# 20160428.net
KiCad netlist of a schematic drawn in Altium Designer
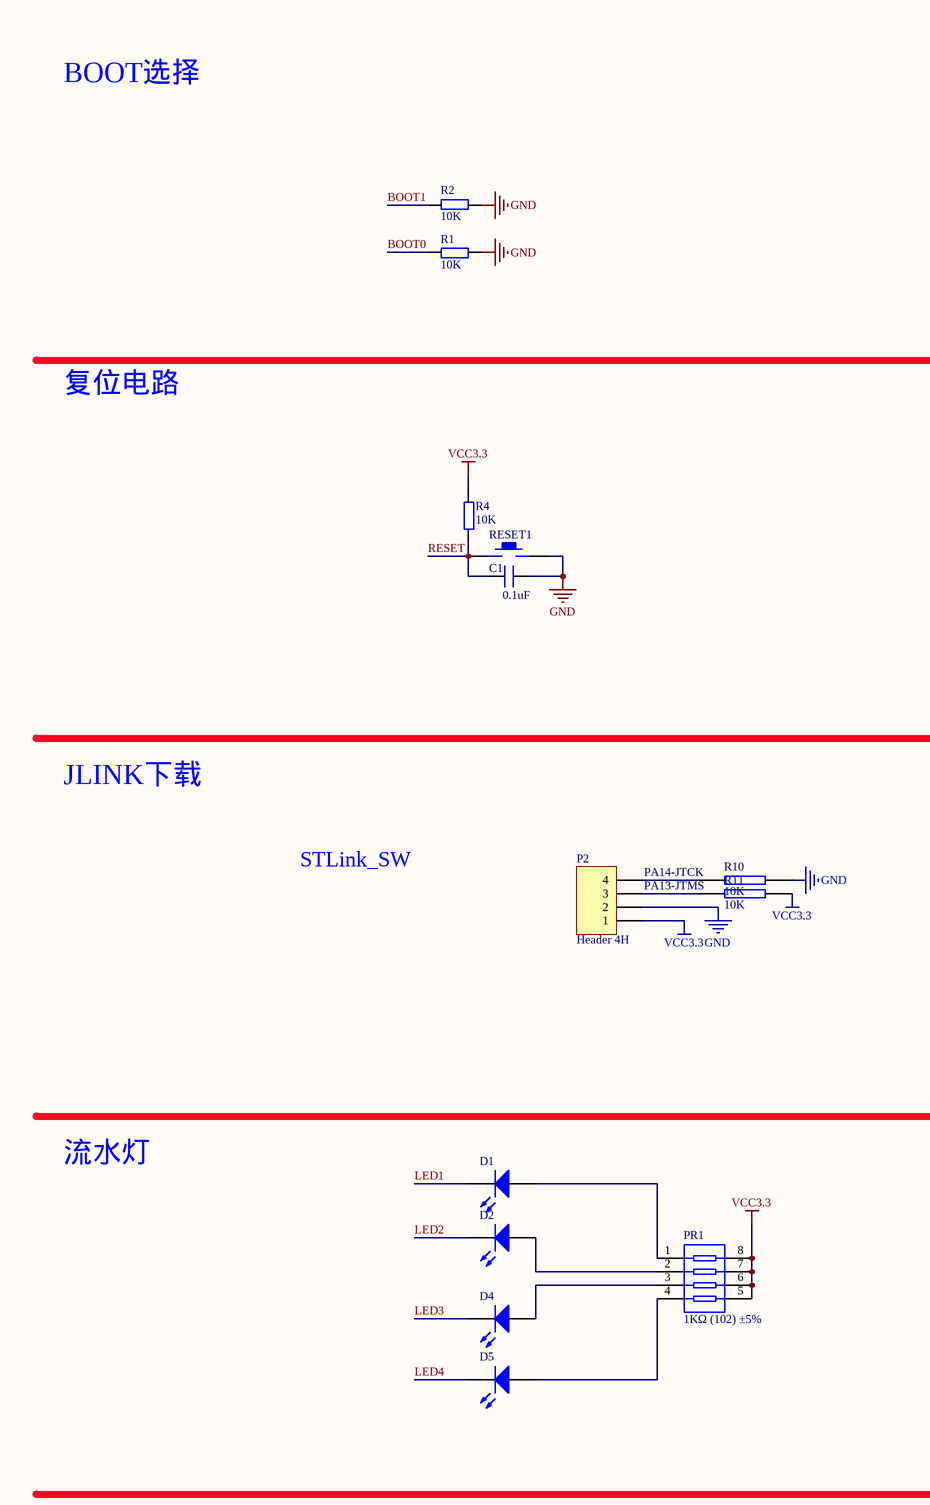
[diagram p0: 主控板20160428.SchDoc, top left]
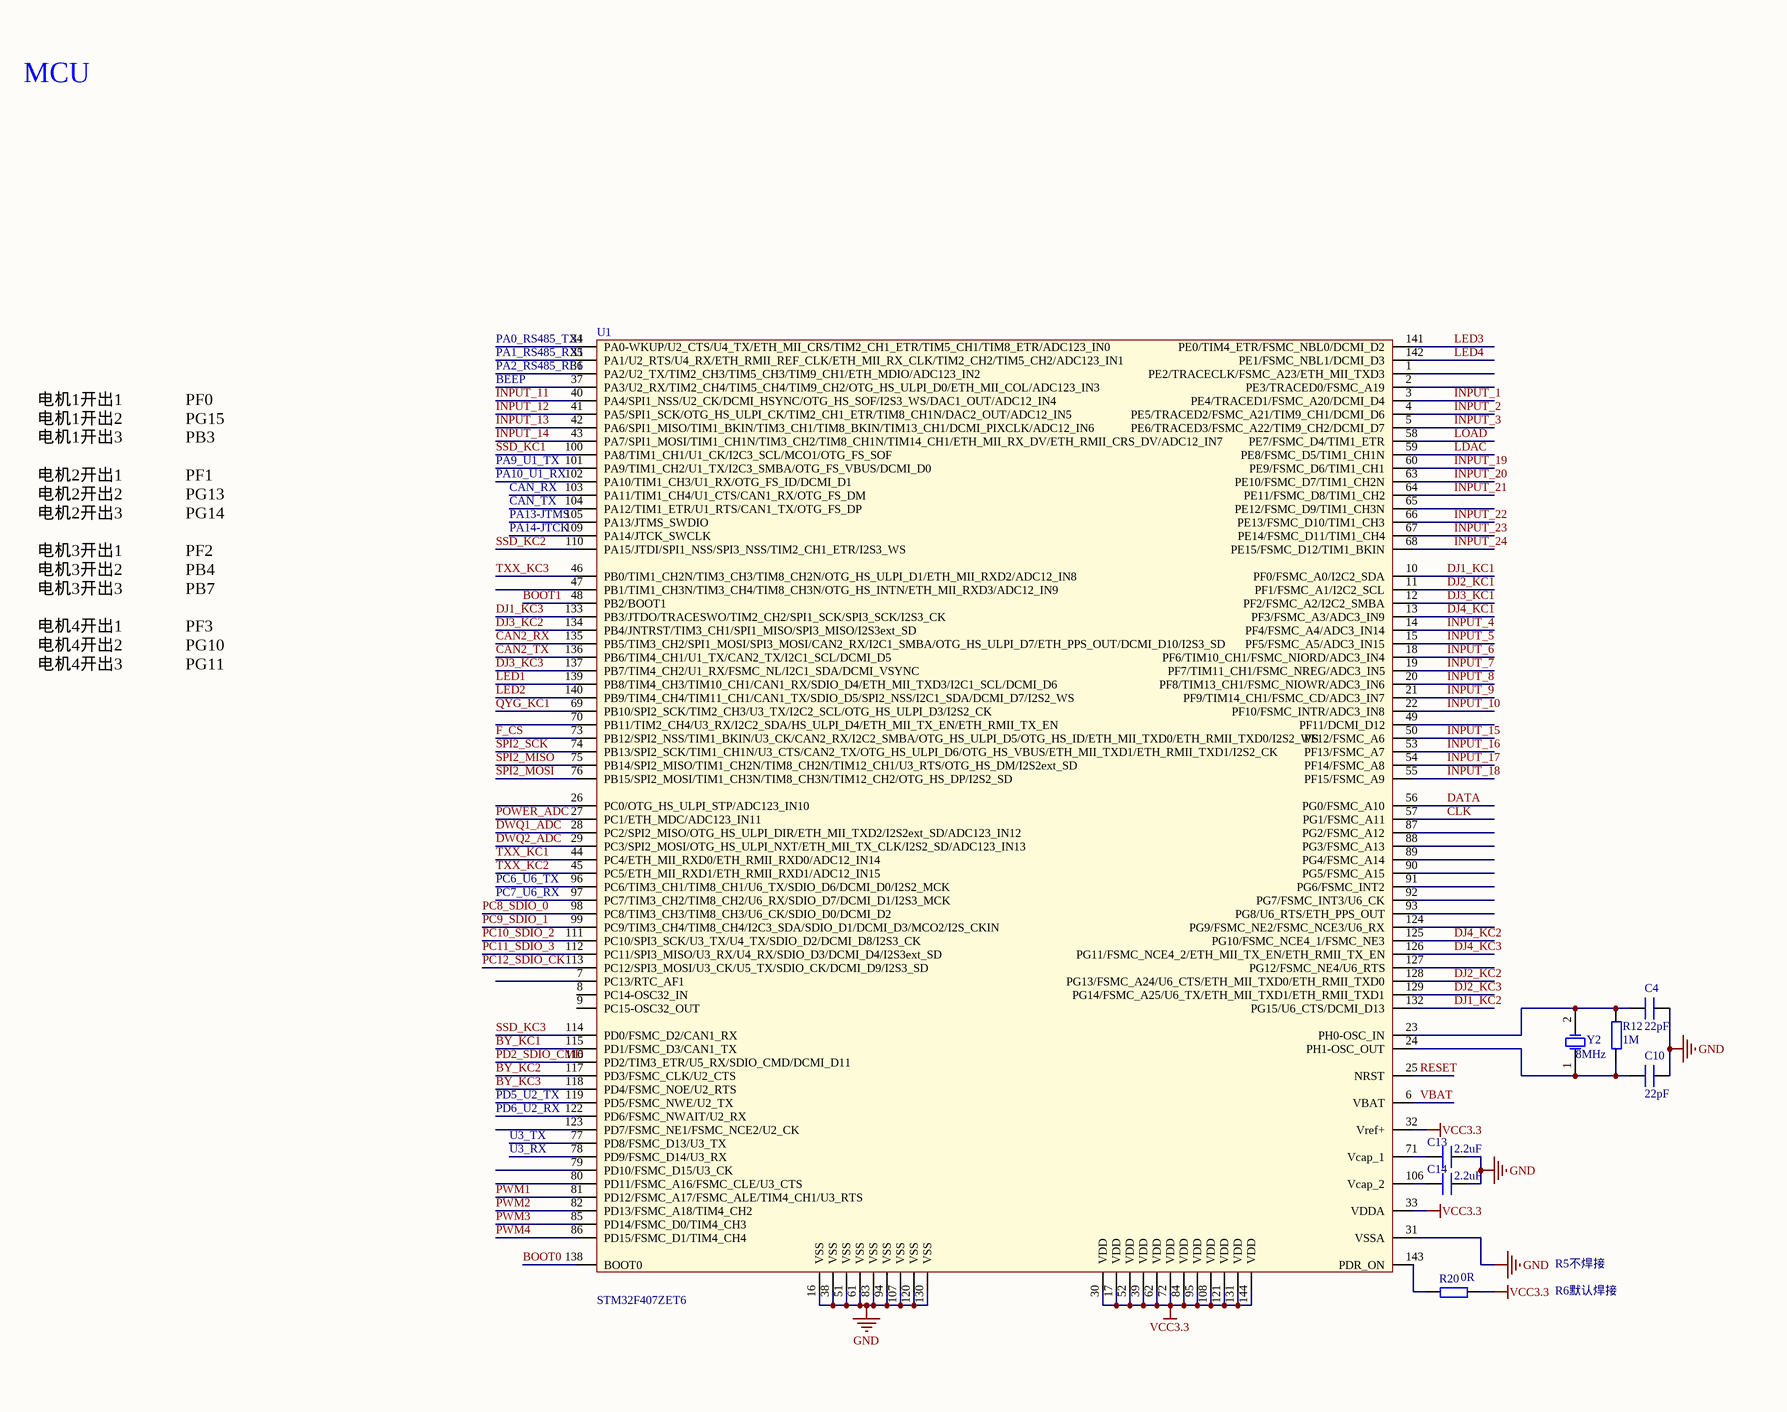
[diagram p1: 主控板20160428.SchDoc, top middle]
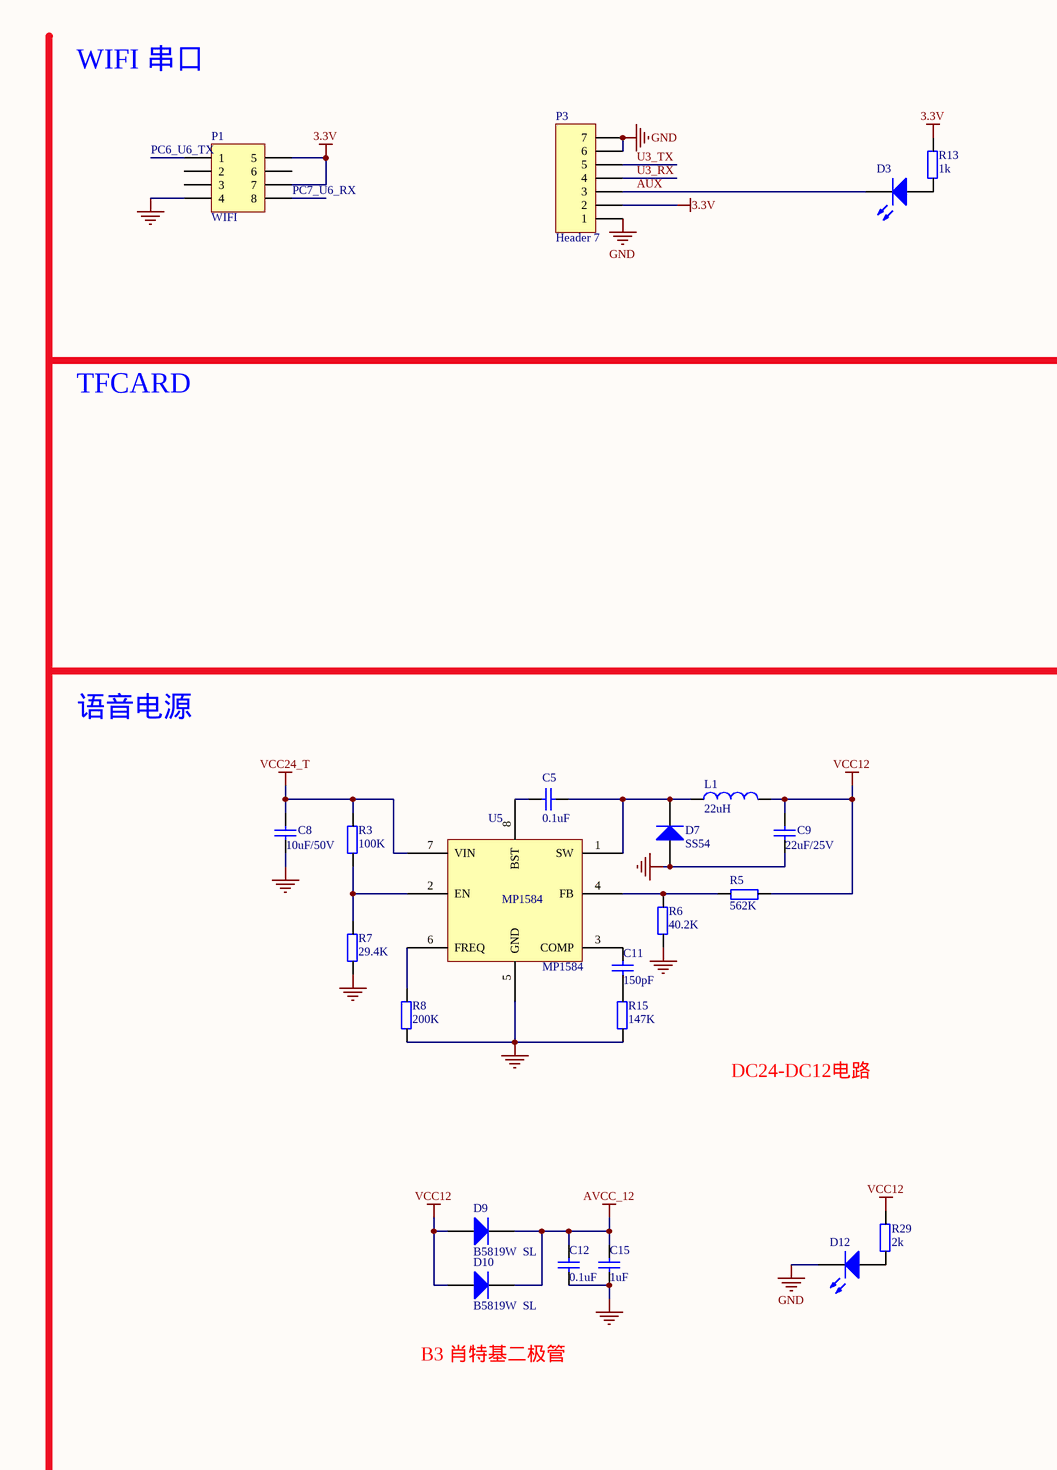
[diagram p2: 主控板20160428.SchDoc, top right]
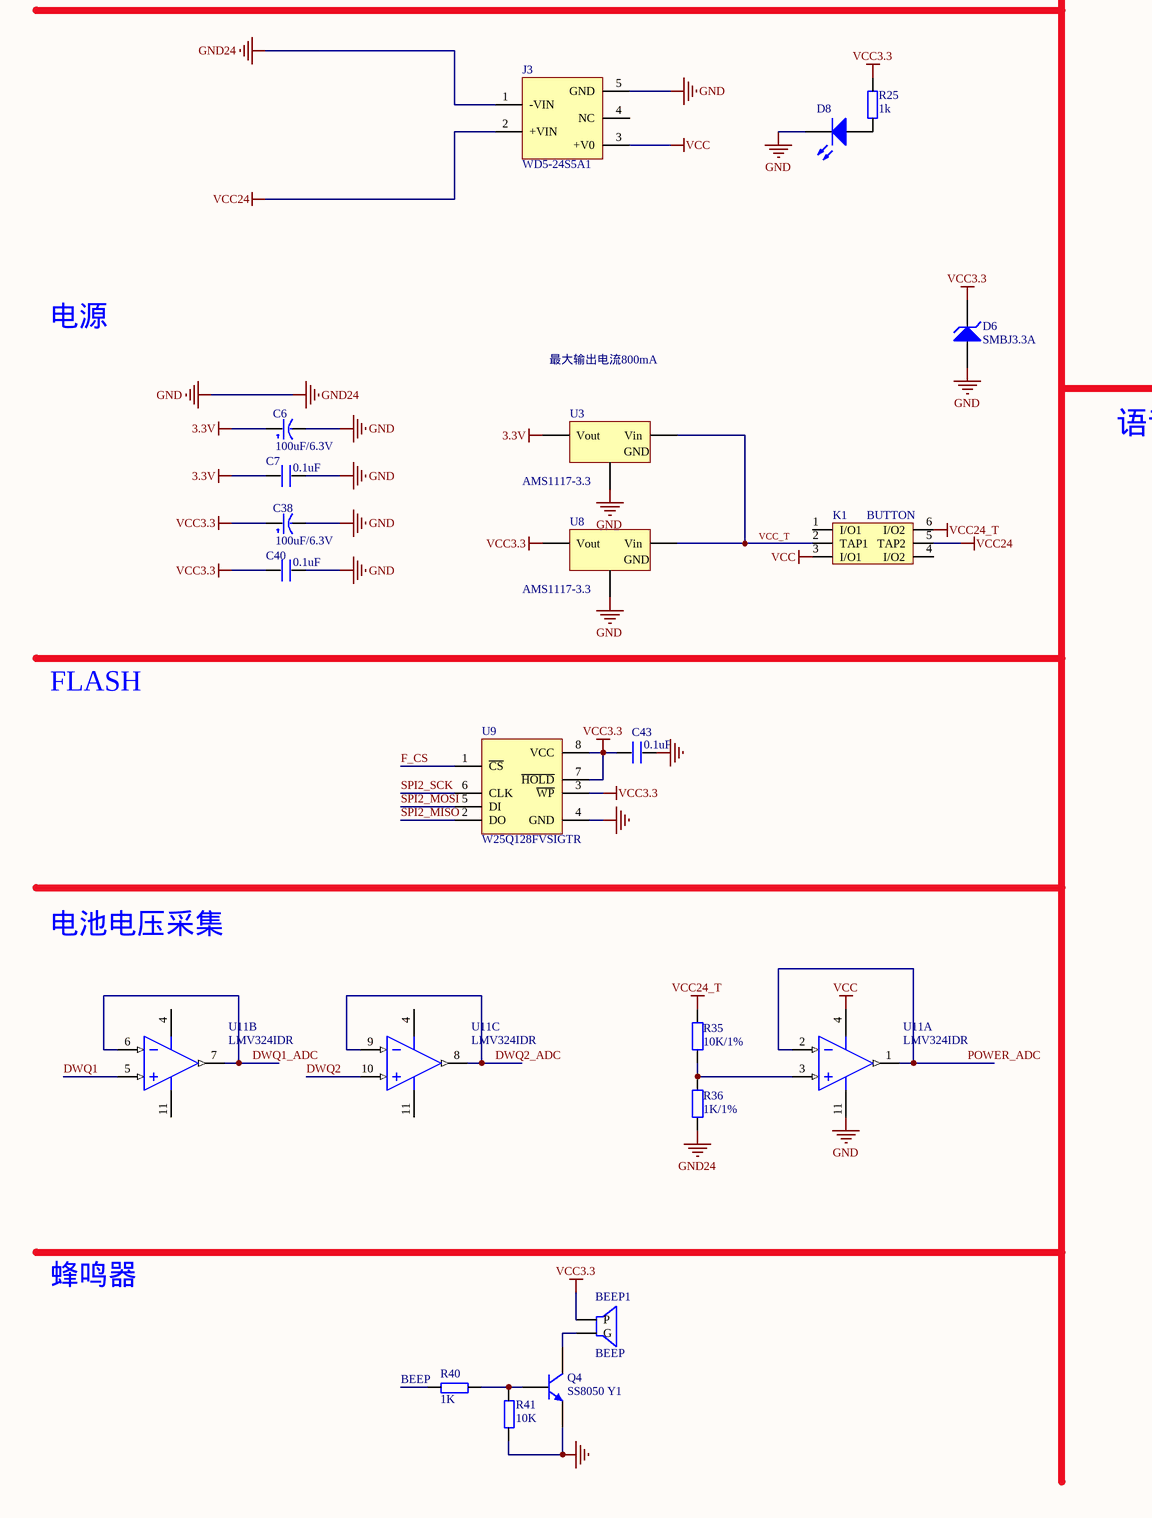
[diagram p3: 主控板20160428.SchDoc, bottom left]
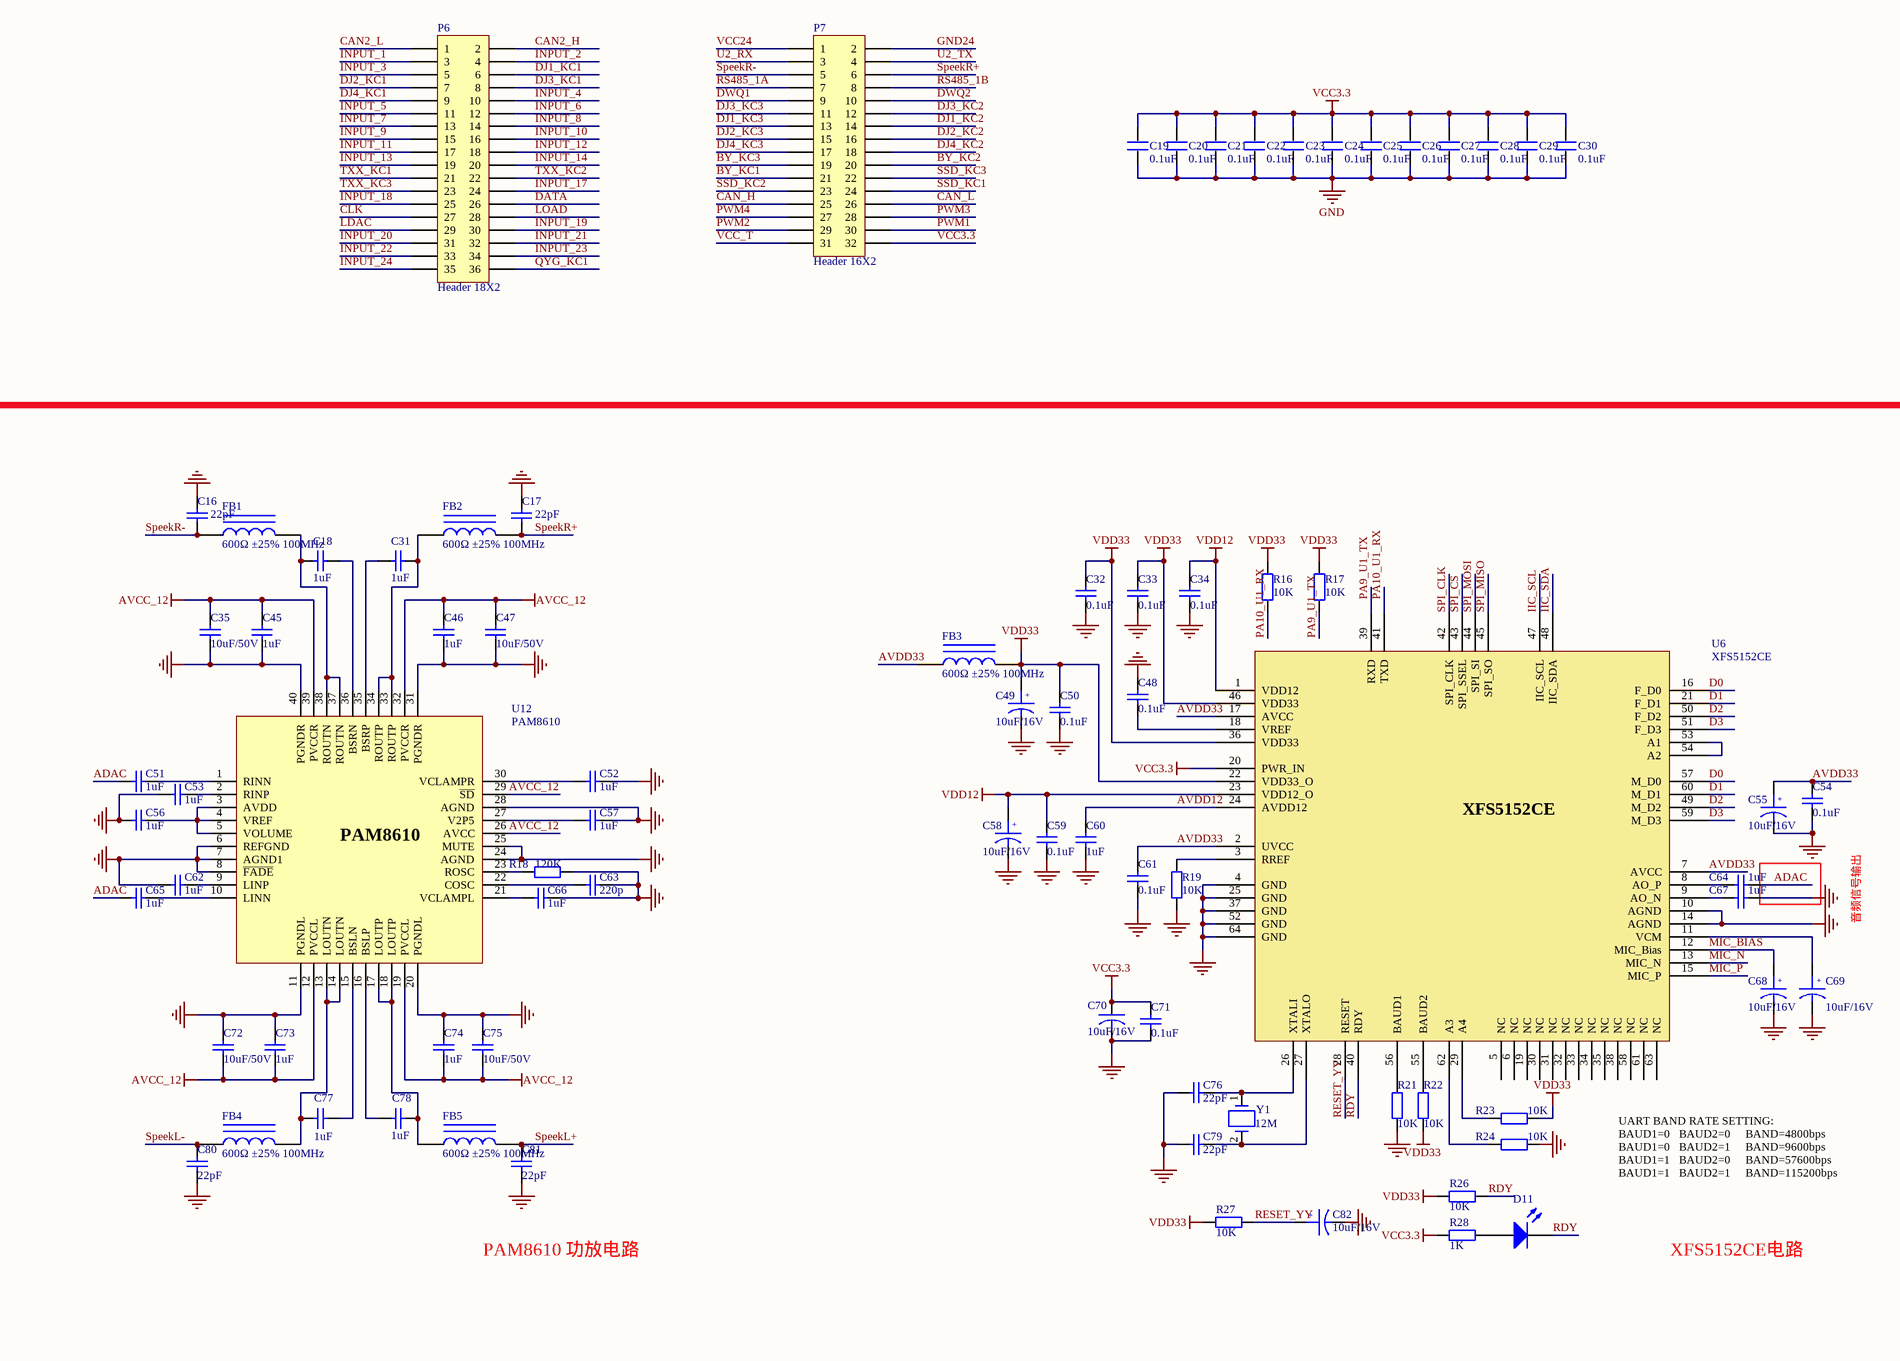
[diagram p4: 主控板20160428.SchDoc, bottom middle]
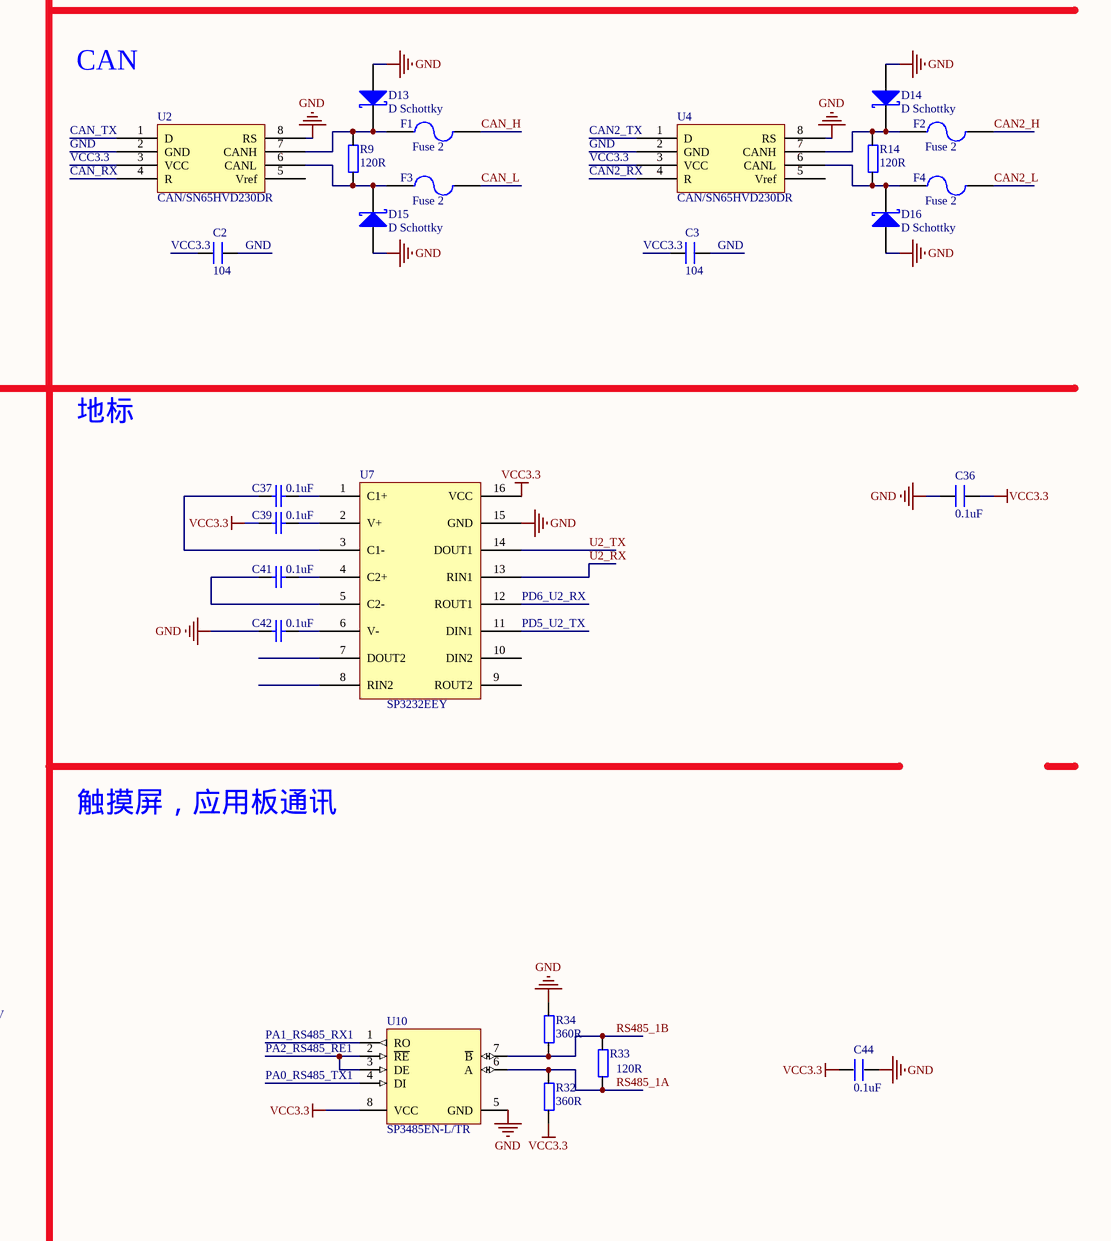
[diagram p5: 主控板20160428.SchDoc, bottom right]

(export (version "E")
  (design (tool "Eeschema 10.0.6"))
  (components
    (comp (ref "BEEP1") (value "BEEP") (footprint "BELL-5") (libsource (lib "WarShip V3_SCH") (part "BEEP")))
    (comp (ref "C1") (value "0.1uF") (footprint "C0805") (libsource (lib "Explorer STM32F407封装库") (part "C")))
    (comp (ref "C2") (value "104") (footprint "C0805") (libsource (lib "Explorer STM32F407封装库") (part "C_3")))
    (comp (ref "C3") (value "104") (footprint "C0805") (libsource (lib "Explorer STM32F407封装库") (part "C_3")))
    (comp (ref "C4")
      (value "22pF")
      (footprint "C0805")
      (libsource (lib "Explorer STM32F407封装库") (part "C_3"))
    )
    (comp (ref "C5")
      (value "0.1uF")
      (footprint "0603_C")
      (description "Capacitor (Semiconductor SIM Model)")
      (fields (field (name "PUBLISHER") "Altium Limited"))
      (libsource (lib "Miscellaneous Devices") (part "Cap Semi"))
    )
    (comp (ref "C6")
      (value "100uF/6.3V")
      (footprint "CASE-B_3528")
      (libsource (lib "WarShip V3_SCH") (part "CAP"))
    )
    (comp (ref "C7") (value "0.1uF") (footprint "C0805") (libsource (lib "WarShip V3_SCH") (part "C")))
    (comp (ref "C8")
      (value "10uF/50V")
      (footprint "1206_C")
      (description "Capacitor (Semiconductor SIM Model)")
      (fields (field (name "PUBLISHER") "Altium Limited"))
      (libsource (lib "Miscellaneous Devices") (part "Cap Semi"))
    )
    (comp (ref "C9")
      (value "22uF/25V")
      (footprint "0805_C")
      (description "Capacitor (Semiconductor SIM Model)")
      (fields (field (name "PUBLISHER") "Altium Limited"))
      (libsource (lib "Miscellaneous Devices") (part "Cap Semi"))
    )
    (comp (ref "C10")
      (value "22pF")
      (footprint "C0805")
      (libsource (lib "Explorer STM32F407封装库") (part "C_3"))
    )
    (comp (ref "C11")
      (value "150pF")
      (footprint "0603_C")
      (description "Capacitor (Semiconductor SIM Model)")
      (fields (field (name "PUBLISHER") "Altium Limited"))
      (libsource (lib "Miscellaneous Devices") (part "Cap Semi"))
    )
    (comp (ref "C12")
      (value "0.1uF")
      (footprint "0603_C")
      (description "Capacitor (Semiconductor SIM Model)")
      (fields (field (name "PUBLISHER") "Altium Limited"))
      (libsource (lib "Miscellaneous Devices") (part "Cap Semi"))
    )
    (comp (ref "C13")
      (value "2.2uF")
      (footprint "C0805")
      (libsource (lib "Explorer STM32F407封装库") (part "C"))
    )
    (comp (ref "C14")
      (value "2.2uF")
      (footprint "C0805")
      (libsource (lib "Explorer STM32F407封装库") (part "C"))
    )
    (comp (ref "C15")
      (value "1uF")
      (footprint "0603_C")
      (description "Capacitor (Semiconductor SIM Model)")
      (fields (field (name "PUBLISHER") "Altium Limited"))
      (libsource (lib "Miscellaneous Devices") (part "Cap Semi"))
    )
    (comp (ref "C16")
      (value "22pF")
      (footprint "0603_C")
      (description "Capacitor (Semiconductor SIM Model)")
      (fields (field (name "PUBLISHER") "Altium Limited"))
      (libsource (lib "Miscellaneous Devices") (part "Cap Semi"))
    )
    (comp (ref "C17")
      (value "22pF")
      (footprint "0603_C")
      (description "Capacitor (Semiconductor SIM Model)")
      (fields (field (name "PUBLISHER") "Altium Limited"))
      (libsource (lib "Miscellaneous Devices") (part "Cap Semi"))
    )
    (comp (ref "C18")
      (value "1uF")
      (footprint "0603_C")
      (description "Capacitor (Semiconductor SIM Model)")
      (fields (field (name "PUBLISHER") "Altium Limited"))
      (libsource (lib "Miscellaneous Devices") (part "Cap Semi"))
    )
    (comp (ref "C19") (value "0.1uF") (footprint "C0805") (libsource (lib "WarShip V3_SCH") (part "C")))
    (comp (ref "C20") (value "0.1uF") (footprint "C0805") (libsource (lib "WarShip V3_SCH") (part "C")))
    (comp (ref "C21") (value "0.1uF") (footprint "C0805") (libsource (lib "WarShip V3_SCH") (part "C")))
    (comp (ref "C22") (value "0.1uF") (footprint "C0805") (libsource (lib "WarShip V3_SCH") (part "C")))
    (comp (ref "C23") (value "0.1uF") (footprint "C0805") (libsource (lib "WarShip V3_SCH") (part "C")))
    (comp (ref "C24") (value "0.1uF") (footprint "C0805") (libsource (lib "WarShip V3_SCH") (part "C")))
    (comp (ref "C25") (value "0.1uF") (footprint "C0805") (libsource (lib "WarShip V3_SCH") (part "C")))
    (comp (ref "C26") (value "0.1uF") (footprint "C0805") (libsource (lib "WarShip V3_SCH") (part "C")))
    (comp (ref "C27") (value "0.1uF") (footprint "C0805") (libsource (lib "WarShip V3_SCH") (part "C")))
    (comp (ref "C28") (value "0.1uF") (footprint "C0805") (libsource (lib "WarShip V3_SCH") (part "C")))
    (comp (ref "C29") (value "0.1uF") (footprint "C0805") (libsource (lib "WarShip V3_SCH") (part "C")))
    (comp (ref "C30") (value "0.1uF") (footprint "C0805") (libsource (lib "WarShip V3_SCH") (part "C")))
    (comp (ref "C31")
      (value "1uF")
      (footprint "0603_C")
      (description "Capacitor (Semiconductor SIM Model)")
      (fields (field (name "PUBLISHER") "Altium Limited"))
      (libsource (lib "Miscellaneous Devices") (part "Cap Semi"))
    )
    (comp (ref "C32")
      (value "0.1uF")
      (footprint "0603_C")
      (description "Capacitor (Semiconductor SIM Model)")
      (fields (field (name "PUBLISHER") "Altium Limited"))
      (libsource (lib "Miscellaneous Devices") (part "Cap Semi"))
    )
    (comp (ref "C33")
      (value "0.1uF")
      (footprint "0603_C")
      (description "Capacitor (Semiconductor SIM Model)")
      (fields (field (name "PUBLISHER") "Altium Limited"))
      (libsource (lib "Miscellaneous Devices") (part "Cap Semi"))
    )
    (comp (ref "C34")
      (value "0.1uF")
      (footprint "0603_C")
      (description "Capacitor (Semiconductor SIM Model)")
      (fields (field (name "PUBLISHER") "Altium Limited"))
      (libsource (lib "Miscellaneous Devices") (part "Cap Semi"))
    )
    (comp (ref "C35")
      (value "10uF/50V")
      (footprint "1206_C")
      (description "电容")
      (fields (field (name "PUBLISHER") "Altium Limited"))
      (libsource (lib "*") (part "Cap NP"))
    )
    (comp (ref "C36")
      (value "0.1uF")
      (footprint "C0805")
      (libsource (lib "Explorer STM32F407封装库") (part "C_2"))
    )
    (comp (ref "C37")
      (value "0.1uF")
      (footprint "C0805")
      (description "Capacitor")
      (fields (field (name "PUBLISHER") "Altium Limited"))
      (libsource (lib "Miscellaneous Devices") (part "Cap"))
    )
    (comp (ref "C38")
      (value "100uF/6.3V")
      (footprint "CASE-B_3528")
      (libsource (lib "WarShip V3_SCH") (part "CAP"))
    )
    (comp (ref "C39")
      (value "0.1uF")
      (footprint "C0805")
      (description "Capacitor")
      (fields (field (name "PUBLISHER") "Altium Limited"))
      (libsource (lib "Miscellaneous Devices") (part "Cap"))
    )
    (comp (ref "C40") (value "0.1uF") (footprint "C0805") (libsource (lib "WarShip V3_SCH") (part "C")))
    (comp (ref "C41")
      (value "0.1uF")
      (footprint "C0805")
      (description "Capacitor")
      (fields (field (name "PUBLISHER") "Altium Limited"))
      (libsource (lib "Miscellaneous Devices") (part "Cap"))
    )
    (comp (ref "C42")
      (value "0.1uF")
      (footprint "C0805")
      (description "Capacitor")
      (fields (field (name "PUBLISHER") "Altium Limited"))
      (libsource (lib "Miscellaneous Devices") (part "Cap"))
    )
    (comp (ref "C43") (value "0.1uF") (footprint "C0805") (libsource (lib "WarShip V3_SCH") (part "C")))
    (comp (ref "C44")
      (value "0.1uF")
      (footprint "C0805")
      (libsource (lib "Explorer STM32F407封装库") (part "C_3"))
    )
    (comp (ref "C45")
      (value "1uF")
      (footprint "0603_C")
      (description "Capacitor (Semiconductor SIM Model)")
      (fields (field (name "PUBLISHER") "Altium Limited"))
      (libsource (lib "Miscellaneous Devices") (part "Cap Semi"))
    )
    (comp (ref "C46")
      (value "1uF")
      (footprint "0603_C")
      (description "Capacitor (Semiconductor SIM Model)")
      (fields (field (name "PUBLISHER") "Altium Limited"))
      (libsource (lib "Miscellaneous Devices") (part "Cap Semi"))
    )
    (comp (ref "C47")
      (value "10uF/50V")
      (footprint "1206_C")
      (description "电容")
      (fields (field (name "PUBLISHER") "Altium Limited"))
      (libsource (lib "*") (part "Cap NP"))
    )
    (comp (ref "C48")
      (value "0.1uF")
      (footprint "0603_C")
      (description "Capacitor (Semiconductor SIM Model)")
      (fields (field (name "PUBLISHER") "Altium Limited"))
      (libsource (lib "Miscellaneous Devices") (part "Cap Semi"))
    )
    (comp (ref "C49") (value "10uF/16V") (footprint "3216") (libsource (lib "*") (part "CAP POL")))
    (comp (ref "C50")
      (value "0.1uF")
      (footprint "0603_C")
      (description "Capacitor (Semiconductor SIM Model)")
      (fields (field (name "PUBLISHER") "Altium Limited"))
      (libsource (lib "Miscellaneous Devices") (part "Cap Semi"))
    )
    (comp (ref "C51")
      (value "1uF")
      (footprint "0603_C")
      (description "Capacitor (Semiconductor SIM Model)")
      (fields (field (name "PUBLISHER") "Altium Limited"))
      (libsource (lib "Miscellaneous Devices") (part "Cap Semi"))
    )
    (comp (ref "C52")
      (value "1uF")
      (footprint "0603_C")
      (description "Capacitor (Semiconductor SIM Model)")
      (fields (field (name "PUBLISHER") "Altium Limited"))
      (libsource (lib "Miscellaneous Devices") (part "Cap Semi"))
    )
    (comp (ref "C53")
      (value "1uF")
      (footprint "0603_C")
      (description "Capacitor (Semiconductor SIM Model)")
      (fields (field (name "PUBLISHER") "Altium Limited"))
      (libsource (lib "Miscellaneous Devices") (part "Cap Semi"))
    )
    (comp (ref "C54")
      (value "0.1uF")
      (footprint "0603_C")
      (description "Capacitor (Semiconductor SIM Model)")
      (fields (field (name "PUBLISHER") "Altium Limited"))
      (libsource (lib "Miscellaneous Devices") (part "Cap Semi"))
    )
    (comp (ref "C55") (value "10uF/16V") (footprint "3216") (libsource (lib "*") (part "CAP POL")))
    (comp (ref "C56")
      (value "1uF")
      (footprint "0603_C")
      (description "Capacitor (Semiconductor SIM Model)")
      (fields (field (name "PUBLISHER") "Altium Limited"))
      (libsource (lib "Miscellaneous Devices") (part "Cap Semi"))
    )
    (comp (ref "C57")
      (value "1uF")
      (footprint "0603_C")
      (description "Capacitor (Semiconductor SIM Model)")
      (fields (field (name "PUBLISHER") "Altium Limited"))
      (libsource (lib "Miscellaneous Devices") (part "Cap Semi"))
    )
    (comp (ref "C58") (value "10uF/16V") (footprint "3216") (libsource (lib "*") (part "CAP POL")))
    (comp (ref "C59")
      (value "0.1uF")
      (footprint "0603_C")
      (description "Capacitor (Semiconductor SIM Model)")
      (fields (field (name "PUBLISHER") "Altium Limited"))
      (libsource (lib "Miscellaneous Devices") (part "Cap Semi"))
    )
    (comp (ref "C60")
      (value "1uF")
      (footprint "0603_C")
      (description "Capacitor (Semiconductor SIM Model)")
      (fields (field (name "PUBLISHER") "Altium Limited"))
      (libsource (lib "Miscellaneous Devices") (part "Cap Semi"))
    )
    (comp (ref "C61")
      (value "0.1uF")
      (footprint "0603_C")
      (description "Capacitor (Semiconductor SIM Model)")
      (fields (field (name "PUBLISHER") "Altium Limited"))
      (libsource (lib "Miscellaneous Devices") (part "Cap Semi"))
    )
    (comp (ref "C62")
      (value "1uF")
      (footprint "0603_C")
      (description "Capacitor (Semiconductor SIM Model)")
      (fields (field (name "PUBLISHER") "Altium Limited"))
      (libsource (lib "Miscellaneous Devices") (part "Cap Semi"))
    )
    (comp (ref "C63")
      (value "220p")
      (footprint "0603_C")
      (description "Capacitor (Semiconductor SIM Model)")
      (fields (field (name "PUBLISHER") "Altium Limited"))
      (libsource (lib "Miscellaneous Devices") (part "Cap Semi"))
    )
    (comp (ref "C64")
      (value "1uF")
      (footprint "0603_C")
      (description "Capacitor (Semiconductor SIM Model)")
      (fields (field (name "PUBLISHER") "Altium Limited"))
      (libsource (lib "Miscellaneous Devices") (part "Cap Semi"))
    )
    (comp (ref "C65")
      (value "1uF")
      (footprint "0603_C")
      (description "Capacitor (Semiconductor SIM Model)")
      (fields (field (name "PUBLISHER") "Altium Limited"))
      (libsource (lib "Miscellaneous Devices") (part "Cap Semi"))
    )
    (comp (ref "C66")
      (value "1uF")
      (footprint "0603_C")
      (description "Capacitor (Semiconductor SIM Model)")
      (fields (field (name "PUBLISHER") "Altium Limited"))
      (libsource (lib "Miscellaneous Devices") (part "Cap Semi"))
    )
    (comp (ref "C67")
      (value "1uF")
      (footprint "0603_C")
      (description "Capacitor (Semiconductor SIM Model)")
      (fields (field (name "PUBLISHER") "Altium Limited"))
      (libsource (lib "Miscellaneous Devices") (part "Cap Semi"))
    )
    (comp (ref "C68") (value "10uF/16V") (footprint "3216") (libsource (lib "*") (part "CAP POL")))
    (comp (ref "C69") (value "10uF/16V") (footprint "3216") (libsource (lib "*") (part "CAP POL")))
    (comp (ref "C70")
      (value "10uF/16V")
      (footprint "3216")
      (description "Capacitor")
      (libsource (lib "*") (part "CAPACITOR"))
    )
    (comp (ref "C71")
      (value "0.1uF")
      (footprint "0603_C")
      (description "Capacitor (Semiconductor SIM Model)")
      (fields (field (name "PUBLISHER") "Altium Limited"))
      (libsource (lib "Miscellaneous Devices") (part "Cap Semi"))
    )
    (comp (ref "C72")
      (value "10uF/50V")
      (footprint "1206_C")
      (description "电容")
      (fields (field (name "PUBLISHER") "Altium Limited"))
      (libsource (lib "*") (part "Cap NP"))
    )
    (comp (ref "C73")
      (value "1uF")
      (footprint "0603_C")
      (description "Capacitor (Semiconductor SIM Model)")
      (fields (field (name "PUBLISHER") "Altium Limited"))
      (libsource (lib "Miscellaneous Devices") (part "Cap Semi"))
    )
    (comp (ref "C74")
      (value "1uF")
      (footprint "0603_C")
      (description "Capacitor (Semiconductor SIM Model)")
      (fields (field (name "PUBLISHER") "Altium Limited"))
      (libsource (lib "Miscellaneous Devices") (part "Cap Semi"))
    )
    (comp (ref "C75")
      (value "10uF/50V")
      (footprint "1206_C")
      (description "电容")
      (fields (field (name "PUBLISHER") "Altium Limited"))
      (libsource (lib "*") (part "Cap NP"))
    )
    (comp (ref "C76")
      (value "22pF")
      (footprint "0603_C")
      (description "电容")
      (fields (field (name "PUBLISHER") "Altium Limited"))
      (libsource (lib "*") (part "Cap NP"))
    )
    (comp (ref "C77")
      (value "1uF")
      (footprint "0603_C")
      (description "Capacitor (Semiconductor SIM Model)")
      (fields (field (name "PUBLISHER") "Altium Limited"))
      (libsource (lib "Miscellaneous Devices") (part "Cap Semi"))
    )
    (comp (ref "C78")
      (value "1uF")
      (footprint "0603_C")
      (description "Capacitor (Semiconductor SIM Model)")
      (fields (field (name "PUBLISHER") "Altium Limited"))
      (libsource (lib "Miscellaneous Devices") (part "Cap Semi"))
    )
    (comp (ref "C79")
      (value "22pF")
      (footprint "0603_C")
      (description "电容")
      (fields (field (name "PUBLISHER") "Altium Limited"))
      (libsource (lib "*") (part "Cap NP"))
    )
    (comp (ref "C80")
      (value "22pF")
      (footprint "0603_C")
      (description "Capacitor (Semiconductor SIM Model)")
      (fields (field (name "PUBLISHER") "Altium Limited"))
      (libsource (lib "Miscellaneous Devices") (part "Cap Semi"))
    )
    (comp (ref "C81")
      (value "22pF")
      (footprint "0603_C")
      (description "Capacitor (Semiconductor SIM Model)")
      (fields (field (name "PUBLISHER") "Altium Limited"))
      (libsource (lib "Miscellaneous Devices") (part "Cap Semi"))
    )
    (comp (ref "C82") (value "10uF/16V") (footprint "3216") (libsource (lib "*") (part "CAP POL")))
    (comp (ref "D1")
      (value "红灯 0805")
      (footprint "LC-0805_LED_S1")
      (description "Typical INFRARED GaAs LED")
      (fields (field (name "PUBLISHER") "Altium Limited"))
      (libsource (lib "继电器板_1") (part "LED0"))
    )
    (comp (ref "D2")
      (value "红灯 0805")
      (footprint "LC-0805_LED_S1")
      (description "Typical INFRARED GaAs LED")
      (fields (field (name "PUBLISHER") "Altium Limited"))
      (libsource (lib "继电器板_1") (part "LED0"))
    )
    (comp (ref "D3")
      (value "红灯 0805")
      (footprint "LC-0805_LED_S1")
      (description "Typical INFRARED GaAs LED")
      (fields (field (name "PUBLISHER") "Altium Limited"))
      (libsource (lib "继电器板_1") (part "LED0"))
    )
    (comp (ref "D4")
      (value "红灯 0805")
      (footprint "LC-0805_LED_S1")
      (description "Typical INFRARED GaAs LED")
      (fields (field (name "PUBLISHER") "Altium Limited"))
      (libsource (lib "继电器板_1") (part "LED0"))
    )
    (comp (ref "D5")
      (value "红灯 0805")
      (footprint "LC-0805_LED_S1")
      (description "Typical INFRARED GaAs LED")
      (fields (field (name "PUBLISHER") "Altium Limited"))
      (libsource (lib "继电器板_1") (part "LED0"))
    )
    (comp (ref "D6")
      (value "SMBJ3.3A")
      (footprint "SMB(DO-214AA)_S1")
      (description "Zener Diode")
      (fields (field (name "PUBLISHER") "Altium Limited"))
      (libsource (lib "Miscellaneous Devices") (part "D Zener"))
    )
    (comp (ref "D7")
      (value "SS54")
      (footprint "SMA(DO-214AC)_S1")
      (description "二极管")
      (libsource (lib "Miscellaneous Devices LC") (part "SMA(DO-214AC) SS54"))
    )
    (comp (ref "D8")
      (value "蓝灯 0805")
      (footprint "LC-0805_LED_S1")
      (description "Typical INFRARED GaAs LED")
      (fields (field (name "PUBLISHER") "Altium Limited"))
      (libsource (lib "继电器板_1") (part "LED0"))
    )
    (comp (ref "D9")
      (value "B5819W  SL")
      (footprint "SOD-123")
      (description "肖特基二极管")
      (libsource (lib "Miscellaneous Devices LC") (part "SOD-123 B5819W  SL"))
    )
    (comp (ref "D10")
      (value "B5819W  SL")
      (footprint "SOD-123")
      (description "肖特基二极管")
      (libsource (lib "Miscellaneous Devices LC") (part "SOD-123 B5819W  SL"))
    )
    (comp (ref "D11")
      (value "红灯 0805")
      (footprint "LC-0805_LED_S1")
      (description "Typical INFRARED GaAs LED")
      (fields (field (name "PUBLISHER") "Altium Limited"))
      (libsource (lib "继电器板_1") (part "LED0"))
    )
    (comp (ref "D12")
      (value "蓝灯 0805")
      (footprint "LC-0805_LED_S1")
      (description "Typical INFRARED GaAs LED")
      (fields (field (name "PUBLISHER") "Altium Limited"))
      (libsource (lib "继电器板_1") (part "LED0"))
    )
    (comp (ref "D13")
      (value "D Schottky")
      (footprint "SMB")
      (description "Schottky Diode")
      (fields (field (name "PUBLISHER") "Altium Limited"))
      (libsource (lib "Miscellaneous Devices") (part "D Schottky"))
    )
    (comp (ref "D14")
      (value "D Schottky")
      (footprint "SMB")
      (description "Schottky Diode")
      (fields (field (name "PUBLISHER") "Altium Limited"))
      (libsource (lib "Miscellaneous Devices") (part "D Schottky"))
    )
    (comp (ref "D15")
      (value "D Schottky")
      (footprint "SMB")
      (description "Schottky Diode")
      (fields (field (name "PUBLISHER") "Altium Limited"))
      (libsource (lib "Miscellaneous Devices") (part "D Schottky"))
    )
    (comp (ref "D16")
      (value "D Schottky")
      (footprint "SMB")
      (description "Schottky Diode")
      (fields (field (name "PUBLISHER") "Altium Limited"))
      (libsource (lib "Miscellaneous Devices") (part "D Schottky"))
    )
    (comp (ref "F1")
      (value "Fuse 2")
      (footprint "12Z-2010")
      (description "Fuse")
      (fields (field (name "PUBLISHER") "Altium Limited"))
      (libsource (lib "Miscellaneous Devices") (part "Fuse 2"))
    )
    (comp (ref "F2")
      (value "Fuse 2")
      (footprint "12Z-2010")
      (description "Fuse")
      (fields (field (name "PUBLISHER") "Altium Limited"))
      (libsource (lib "Miscellaneous Devices") (part "Fuse 2"))
    )
    (comp (ref "F3")
      (value "Fuse 2")
      (footprint "12Z-2010")
      (description "Fuse")
      (fields (field (name "PUBLISHER") "Altium Limited"))
      (libsource (lib "Miscellaneous Devices") (part "Fuse 2"))
    )
    (comp (ref "F4")
      (value "Fuse 2")
      (footprint "12Z-2010")
      (description "Fuse")
      (fields (field (name "PUBLISHER") "Altium Limited"))
      (libsource (lib "Miscellaneous Devices") (part "Fuse 2"))
    )
    (comp (ref "FB1")
      (value "600Ω ±25% 100MHz")
      (footprint "0805_L")
      (description "贴片磁珠")
      (libsource (lib "Miscellaneous Devices LC") (part "0805 600Ω 25% 100MHz"))
    )
    (comp (ref "FB2")
      (value "600Ω ±25% 100MHz")
      (footprint "0805_L")
      (description "贴片磁珠")
      (libsource (lib "Miscellaneous Devices LC") (part "0805 600Ω 25% 100MHz"))
    )
    (comp (ref "FB3")
      (value "600Ω ±25% 100MHz")
      (footprint "0805_L")
      (description "贴片磁珠")
      (libsource (lib "Miscellaneous Devices LC") (part "0805 600Ω 25% 100MHz"))
    )
    (comp (ref "FB4")
      (value "600Ω ±25% 100MHz")
      (footprint "0805_L")
      (description "贴片磁珠")
      (libsource (lib "Miscellaneous Devices LC") (part "0805 600Ω 25% 100MHz"))
    )
    (comp (ref "FB5")
      (value "600Ω ±25% 100MHz")
      (footprint "0805_L")
      (description "贴片磁珠")
      (libsource (lib "Miscellaneous Devices LC") (part "0805 600Ω 25% 100MHz"))
    )
    (comp (ref "J3")
      (value "WD5-24S5A1")
      (footprint "WD5-24S3V3")
      (libsource (lib "*") (part "WD5-24S3V3A1"))
    )
    (comp (ref "K1")
      (value "BUTTON")
      (footprint "BTN8.5*8.5")
      (libsource (lib "WarShip V3_SCH") (part "BUTTON"))
    )
    (comp (ref "L1")
      (value "22uH")
      (footprint "L-7*7*4mm-S")
      (description "Inductor")
      (fields (field (name "PUBLISHER") "Altium Limited"))
      (libsource (lib "Miscellaneous Devices") (part "Inductor"))
    )
    (comp (ref "P1")
      (value "WIFI")
      (footprint "HDR2X4_CEN")
      (description "Header, 4-Pin, Dual row")
      (fields (field (name "PUBLISHER") "Altium Limited"))
      (libsource (lib "Miscellaneous Connectors") (part "Header 4X2A"))
    )
    (comp (ref "P2")
      (value "Header 4H")
      (footprint "IDE4")
      (description "Header, 4-Pin, Right Angle")
      (fields (field (name "PUBLISHER") "Altium Limited"))
      (libsource (lib "Miscellaneous Connectors") (part "Header 4H"))
    )
    (comp (ref "P3")
      (value "Header 7")
      (footprint "AS50-T27")
      (description "Header, 7-Pin")
      (fields (field (name "PUBLISHER") "Altium Limited"))
      (libsource (lib "Miscellaneous Connectors") (part "Header 7"))
    )
    (comp (ref "P6")
      (value "Header 18X2")
      (footprint "HDR2X18")
      (description "Header, 18-Pin, Dual row")
      (fields (field (name "PUBLISHER") "Altium Limited"))
      (libsource (lib "Miscellaneous Connectors") (part "Header 18X2"))
    )
    (comp (ref "P7")
      (value "Header 16X2")
      (footprint "HDR2X16")
      (description "Header, 16-Pin, Dual row")
      (fields (field (name "PUBLISHER") "Altium Limited"))
      (libsource (lib "Miscellaneous Connectors") (part "Header 16X2"))
    )
    (comp (ref "PR1")
      (value "1KΩ (102) ±5%")
      (footprint "0603_Rx4")
      (description "贴片排阻")
      (libsource (lib "Miscellaneous Devices LC") (part "0603*4  1KΩ (102) 5%"))
    )
    (comp (ref "Q4")
      (value "SS8050 Y1")
      (footprint "SOT-23(SOT-23-3)")
      (description "三极管")
      (libsource (lib "Miscellaneous Devices LC") (part "SOT-23 SS8050 Y1"))
    )
    (comp (ref "R1")
      (value "10K")
      (footprint "0805_R")
      (libsource (lib "Explorer STM32F407封装库") (part "R_1"))
    )
    (comp (ref "R2")
      (value "10K")
      (footprint "0805_R")
      (libsource (lib "Explorer STM32F407封装库") (part "R_1"))
    )
    (comp (ref "R3")
      (value "100K")
      (footprint "0603_R")
      (libsource (lib "Explorer STM32F407封装库") (part "R_2"))
    )
    (comp (ref "R4")
      (value "10K")
      (footprint "0805_R")
      (libsource (lib "Explorer STM32F407封装库") (part "R_2"))
    )
    (comp (ref "R5")
      (value "562K")
      (footprint "0603_R")
      (libsource (lib "Explorer STM32F407封装库") (part "R_2"))
    )
    (comp (ref "R6")
      (value "40.2K")
      (footprint "0603_R")
      (libsource (lib "Explorer STM32F407封装库") (part "R_2"))
    )
    (comp (ref "R7")
      (value "29.4K")
      (footprint "0603_R")
      (libsource (lib "Explorer STM32F407封装库") (part "R_2"))
    )
    (comp (ref "R8")
      (value "200K")
      (footprint "0603_R")
      (libsource (lib "Explorer STM32F407封装库") (part "R_2"))
    )
    (comp (ref "R9")
      (value "120R")
      (footprint "0805_R")
      (libsource (lib "Explorer STM32F407封装库") (part "R_2"))
    )
    (comp (ref "R10") (value "10K") (footprint "0805_R") (libsource (lib "*") (part "RES2")))
    (comp (ref "R11") (value "10K") (footprint "0805_R") (libsource (lib "*") (part "RES2")))
    (comp (ref "R12") (value "1M") (footprint "0805_R") (libsource (lib "Explorer STM32F407封装库") (part "R")))
    (comp (ref "R13")
      (value "1k")
      (footprint "0805_R")
      (libsource (lib "Explorer STM32F407封装库") (part "R_2"))
    )
    (comp (ref "R14")
      (value "120R")
      (footprint "0805_R")
      (libsource (lib "Explorer STM32F407封装库") (part "R_2"))
    )
    (comp (ref "R15")
      (value "147K")
      (footprint "0603_R")
      (libsource (lib "Explorer STM32F407封装库") (part "R_2"))
    )
    (comp (ref "R16")
      (value "10K")
      (footprint "0603_R")
      (description "Resistor")
      (fields (field (name "PUBLISHER") "Altium Limited"))
      (libsource (lib "") (part "Res2_2"))
    )
    (comp (ref "R17")
      (value "10K")
      (footprint "0603_R")
      (description "Resistor")
      (fields (field (name "PUBLISHER") "Altium Limited"))
      (libsource (lib "") (part "Res2_1"))
    )
    (comp (ref "R18")
      (value "120K")
      (footprint "0603_R")
      (description "Resistor")
      (fields (field (name "PUBLISHER") "Altium Limited"))
      (libsource (lib "") (part "Res2_3"))
    )
    (comp (ref "R19")
      (value "10K")
      (footprint "0603_R")
      (description "Resistor")
      (fields (field (name "PUBLISHER") "Altium Limited"))
      (libsource (lib "") (part "Res2_2"))
    )
    (comp (ref "R20")
      (value "0R")
      (footprint "0805_R")
      (libsource (lib "Explorer STM32F407封装库") (part "R_2"))
    )
    (comp (ref "R21")
      (value "10K")
      (footprint "0603_R")
      (description "Resistor")
      (fields (field (name "PUBLISHER") "Altium Limited"))
      (libsource (lib "") (part "Res2_1"))
    )
    (comp (ref "R22")
      (value "10K")
      (footprint "0603_R")
      (description "Resistor")
      (fields (field (name "PUBLISHER") "Altium Limited"))
      (libsource (lib "") (part "Res2_1"))
    )
    (comp (ref "R23")
      (value "10K")
      (footprint "0603_R")
      (description "Resistor")
      (fields (field (name "PUBLISHER") "Altium Limited"))
      (libsource (lib "*") (part "Res2"))
    )
    (comp (ref "R24")
      (value "10K")
      (footprint "0603_R")
      (description "Resistor")
      (fields (field (name "PUBLISHER") "Altium Limited"))
      (libsource (lib "") (part "Res2_3"))
    )
    (comp (ref "R25")
      (value "1k")
      (footprint "0805_R")
      (libsource (lib "Explorer STM32F407封装库") (part "R_2"))
    )
    (comp (ref "R26")
      (value "10K")
      (footprint "0603_R")
      (description "Resistor")
      (fields (field (name "PUBLISHER") "Altium Limited"))
      (libsource (lib "*") (part "Res2"))
    )
    (comp (ref "R27")
      (value "10K")
      (footprint "0603_R")
      (description "Resistor")
      (fields (field (name "PUBLISHER") "Altium Limited"))
      (libsource (lib "*") (part "Res2"))
    )
    (comp (ref "R28")
      (value "1K")
      (footprint "0603_R")
      (description "Resistor")
      (fields (field (name "PUBLISHER") "Altium Limited"))
      (libsource (lib "*") (part "Res2"))
    )
    (comp (ref "R29")
      (value "2k")
      (footprint "0603_R")
      (libsource (lib "Explorer STM32F407封装库") (part "R_2"))
    )
    (comp (ref "R32")
      (value "360R")
      (footprint "0603_R")
      (libsource (lib "Explorer STM32F407封装库") (part "R_2"))
    )
    (comp (ref "R33")
      (value "120R")
      (footprint "0805_R")
      (libsource (lib "Explorer STM32F407封装库") (part "R_2"))
    )
    (comp (ref "R34")
      (value "360R")
      (footprint "0603_R")
      (libsource (lib "Explorer STM32F407封装库") (part "R_2"))
    )
    (comp (ref "R35")
      (value "10K/1%")
      (footprint "0805_R")
      (description "Resistor")
      (fields (field (name "PUBLISHER") "Altium Limited"))
      (libsource (lib "Miscellaneous Devices") (part "Res2"))
    )
    (comp (ref "R36")
      (value "1K/1%")
      (footprint "0805_R")
      (description "Resistor")
      (fields (field (name "PUBLISHER") "Altium Limited"))
      (libsource (lib "Miscellaneous Devices") (part "Res2"))
    )
    (comp (ref "R40") (value "1K") (footprint "0805_R") (libsource (lib "WarShip V3_SCH") (part "R")))
    (comp (ref "R41") (value "10K") (footprint "0805_R") (libsource (lib "WarShip V3_SCH") (part "R")))
    (comp (ref "RESET1")
      (value "KEY_M")
      (footprint "SW_PB2_A1")
      (libsource (lib "Explorer STM32F407封装库") (part "KEY_M"))
    )
    (comp (ref "U1")
      (value "STM32F407ZET6")
      (footprint "LQFP144")
      (libsource (lib "Explorer STM32F407封装库") (part "STM32F407ZET6"))
    )
    (comp (ref "U2")
      (value "CAN/SN65HVD230DR")
      (footprint "SOIC-8_150mil")
      (description "CAN")
      (libsource (lib "Miscellaneous Devices LC") (part "CAN/SN65HVD230DR"))
    )
    (comp (ref "U3")
      (value "AMS1117-3.3")
      (footprint "SOT-223")
      (description "低压差线性稳压(LDO)")
      (libsource (lib "Miscellaneous Devices LC") (part "SOT-223 AMS1117-3.3"))
    )
    (comp (ref "U4")
      (value "CAN/SN65HVD230DR")
      (footprint "SOIC-8_150mil")
      (description "CAN")
      (libsource (lib "Miscellaneous Devices LC") (part "CAN/SN65HVD230DR"))
    )
    (comp (ref "U5")
      (value "MP1584")
      (footprint "LC-SOIC-8_EP_150MIL")
      (libsource (lib "磁导航") (part "MP1584EN"))
    )
    (comp (ref "U6")
      (value "XFS5152CE")
      (footprint "LQFP-64_10x10x05P")
      (libsource (lib "*") (part "XFS5152-2"))
    )
    (comp (ref "U7")
      (value "SP3232EEY")
      (footprint "TSSOP-16")
      (description "RS232")
      (libsource (lib "Smart_board_v1") (part "MAX3232CUE"))
    )
    (comp (ref "U8")
      (value "AMS1117-3.3")
      (footprint "SOT-223")
      (description "低压差线性稳压(LDO)")
      (libsource (lib "Miscellaneous Devices LC") (part "SOT-223 AMS1117-3.3"))
    )
    (comp (ref "U9")
      (value "W25Q128FVSIGTR")
      (footprint "SOIC8_W")
      (description "Flash ROM")
      (libsource (lib "fszhang") (part "W25QXX"))
    )
    (comp (ref "U10")
      (value "SP3485EN-L/TR")
      (footprint "SOIC-8_150mil")
      (description "RS-485/RS-422")
      (libsource (lib "Miscellaneous Devices LC") (part "SP3485EN-L/TR"))
    )
    (comp (ref "U11")
      (value "LMV324IDR")
      (footprint "SOIC-14_150mil")
      (description "运放")
      (libsource (lib "Miscellaneous Devices LC") (part "LMV324IDR"))
    )
    (comp (ref "U12")
      (value "PAM8610")
      (footprint "QFN50P600X600X80-40N")
      (libsource (lib "my third") (part "PAM8610功放芯片"))
    )
    (comp (ref "Y1")
      (value "12M")
      (footprint "XTAL_US")
      (description "晶振")
      (libsource (lib "*") (part "XTAL1"))
    )
    (comp (ref "Y2")
      (value "8MHz")
      (footprint "XTAL_US")
      (description "Crystal Oscillator")
      (fields (field (name "PUBLISHER") "Altium Limited"))
      (libsource (lib "Explorer STM32F407封装库") (part "XTAL"))
    )
  )
  (nets
    (net (code "1") (name "/ADAC") (class "Default")
      (node (ref "C51") (pin "1") (pinfunction "1_1") (pintype "passive"))
      (node (ref "C64") (pin "1") (pinfunction "1_1") (pintype "passive"))
      (node (ref "C65") (pin "1") (pinfunction "1_1") (pintype "passive"))
    )
    (net (code "2") (name "/AUX") (class "Default")
      (node (ref "D3") (pin "K") (pinfunction "K_K") (pintype "passive"))
      (node (ref "P3") (pin "3") (pinfunction "3_3") (pintype "passive"))
    )
    (net (code "3") (name "/AVDD12") (class "Default")
      (node (ref "C60") (pin "2") (pinfunction "2_2") (pintype "passive"))
      (node (ref "U6") (pin "24") (pinfunction "AVDD12_24") (pintype "passive"))
    )
    (net (code "4") (name "/AVDD33") (class "Default")
      (node (ref "C54") (pin "1") (pinfunction "1_1") (pintype "passive"))
      (node (ref "C55") (pin "1") (pinfunction "1_1") (pintype "passive"))
      (node (ref "C61") (pin "1") (pinfunction "1_1") (pintype "passive"))
      (node (ref "FB3") (pin "1") (pinfunction "1_1") (pintype "passive"))
      (node (ref "U6") (pin "17") (pinfunction "AVCC_17") (pintype "passive"))
      (node (ref "U6") (pin "2") (pinfunction "UVCC_2") (pintype "passive"))
      (node (ref "U6") (pin "7") (pinfunction "AVCC_7") (pintype "passive"))
    )
    (net (code "5") (name "/BEEP") (class "Default")
      (node (ref "R40") (pin "1") (pintype "passive"))
      (node (ref "U1") (pin "37") (pinfunction "PA3/U2_RX/TIM2_CH4/TIM5_CH4/TIM9_CH2/OTG_HS_ULPI_D0/ETH_MII_COL/ADC123_IN3_37") (pintype "passive"))
    )
    (net (code "6") (name "/BOOT0") (class "Default")
      (node (ref "R1") (pin "1") (pintype "passive"))
      (node (ref "U1") (pin "138") (pinfunction "BOOT0_138") (pintype "passive"))
    )
    (net (code "7") (name "/BOOT1") (class "Default")
      (node (ref "R2") (pin "2") (pintype "passive"))
      (node (ref "U1") (pin "48") (pinfunction "PB2/BOOT1_48") (pintype "passive"))
    )
    (net (code "8") (name "/BY_KC1") (class "Default")
      (node (ref "P7") (pin "21") (pinfunction "21_21") (pintype "passive"))
      (node (ref "U1") (pin "115") (pinfunction "PD1/FSMC_D3/CAN1_TX_115") (pintype "passive"))
    )
    (net (code "9") (name "/BY_KC2") (class "Default")
      (node (ref "P7") (pin "20") (pinfunction "20_20") (pintype "passive"))
      (node (ref "U1") (pin "117") (pinfunction "PD3/FSMC_CLK/U2_CTS_117") (pintype "passive"))
    )
    (net (code "10") (name "/BY_KC3") (class "Default")
      (node (ref "P7") (pin "19") (pinfunction "19_19") (pintype "passive"))
      (node (ref "U1") (pin "118") (pinfunction "PD4/FSMC_NOE/U2_RTS_118") (pintype "passive"))
    )
    (net (code "11") (name "/CAN2_H") (class "Default")
      (node (ref "F2") (pin "1") (pinfunction "1_1") (pintype "passive"))
      (node (ref "P6") (pin "2") (pinfunction "2_2") (pintype "passive"))
    )
    (net (code "12") (name "/CAN2_L") (class "Default")
      (node (ref "F4") (pin "1") (pinfunction "1_1") (pintype "passive"))
      (node (ref "P6") (pin "1") (pinfunction "1_1") (pintype "passive"))
    )
    (net (code "13") (name "/CAN2_RX") (class "Default")
      (node (ref "U1") (pin "135") (pinfunction "PB5/TIM3_CH2/SPI1_MOSI/SPI3_MOSI/CAN2_RX/I2C1_SMBA/OTG_HS_ULPI_D7/ETH_PPS_OUT/DCMI_D10/I2S3_SD_135") (pintype "passive"))
      (node (ref "U4") (pin "4") (pinfunction "R_4") (pintype "passive"))
    )
    (net (code "14") (name "/CAN2_TX") (class "Default")
      (node (ref "U1") (pin "136") (pinfunction "PB6/TIM4_CH1/U1_TX/CAN2_TX/I2C1_SCL/DCMI_D5_136") (pintype "passive"))
      (node (ref "U4") (pin "1") (pinfunction "D_1") (pintype "passive"))
    )
    (net (code "15") (name "/CAN_H") (class "Default")
      (node (ref "F1") (pin "1") (pinfunction "1_1") (pintype "passive"))
      (node (ref "P7") (pin "25") (pinfunction "25_25") (pintype "passive"))
    )
    (net (code "16") (name "/CAN_L") (class "Default")
      (node (ref "F3") (pin "1") (pinfunction "1_1") (pintype "passive"))
      (node (ref "P7") (pin "26") (pinfunction "26_26") (pintype "passive"))
    )
    (net (code "17") (name "/CAN_RX") (class "Default")
      (node (ref "U1") (pin "103") (pinfunction "PA11/TIM1_CH4/U1_CTS/CAN1_RX/OTG_FS_DM_103") (pintype "passive"))
      (node (ref "U2") (pin "4") (pinfunction "R_4") (pintype "passive"))
    )
    (net (code "18") (name "/CAN_TX") (class "Default")
      (node (ref "U1") (pin "104") (pinfunction "PA12/TIM1_ETR/U1_RTS/CAN1_TX/OTG_FS_DP_104") (pintype "passive"))
      (node (ref "U2") (pin "1") (pinfunction "D_1") (pintype "passive"))
    )
    (net (code "19") (name "/CLK") (class "Default")
      (node (ref "P6") (pin "27") (pinfunction "27_27") (pintype "passive"))
      (node (ref "U1") (pin "57") (pinfunction "PG1/FSMC_A11_57") (pintype "passive"))
    )
    (net (code "20") (name "/D0") (class "Default")
      (node (ref "U6") (pin "16") (pinfunction "F_D0_16") (pintype "passive"))
      (node (ref "U6") (pin "57") (pinfunction "M_D0_57") (pintype "passive"))
    )
    (net (code "21") (name "/D1") (class "Default")
      (node (ref "U6") (pin "21") (pinfunction "F_D1_21") (pintype "passive"))
      (node (ref "U6") (pin "60") (pinfunction "M_D1_60") (pintype "passive"))
    )
    (net (code "22") (name "/D2") (class "Default")
      (node (ref "U6") (pin "49") (pinfunction "M_D2_49") (pintype "passive"))
      (node (ref "U6") (pin "50") (pinfunction "F_D2_50") (pintype "passive"))
    )
    (net (code "23") (name "/D3") (class "Default")
      (node (ref "U6") (pin "51") (pinfunction "F_D3_51") (pintype "passive"))
      (node (ref "U6") (pin "59") (pinfunction "M_D3_59") (pintype "passive"))
    )
    (net (code "24") (name "/DATA") (class "Default")
      (node (ref "P6") (pin "26") (pinfunction "26_26") (pintype "passive"))
      (node (ref "U1") (pin "56") (pinfunction "PG0/FSMC_A10_56") (pintype "passive"))
    )
    (net (code "25") (name "/DJ1_KC1") (class "Default")
      (node (ref "P6") (pin "6") (pinfunction "6_6") (pintype "passive"))
      (node (ref "U1") (pin "10") (pinfunction "PF0/FSMC_A0/I2C2_SDA_10") (pintype "passive"))
    )
    (net (code "26") (name "/DJ1_KC2") (class "Default")
      (node (ref "P7") (pin "14") (pinfunction "14_14") (pintype "passive"))
      (node (ref "U1") (pin "132") (pinfunction "PG15/U6_CTS/DCMI_D13_132") (pintype "passive"))
    )
    (net (code "27") (name "/DJ1_KC3") (class "Default")
      (node (ref "P7") (pin "13") (pinfunction "13_13") (pintype "passive"))
      (node (ref "U1") (pin "133") (pinfunction "PB3/JTDO/TRACESWO/TIM2_CH2/SPI1_SCK/SPI3_SCK/I2S3_CK_133") (pintype "passive"))
    )
    (net (code "28") (name "/DJ2_KC1") (class "Default")
      (node (ref "P6") (pin "7") (pinfunction "7_7") (pintype "passive"))
      (node (ref "U1") (pin "11") (pinfunction "PF1/FSMC_A1/I2C2_SCL_11") (pintype "passive"))
    )
    (net (code "29") (name "/DJ2_KC2") (class "Default")
      (node (ref "P7") (pin "16") (pinfunction "16_16") (pintype "passive"))
      (node (ref "U1") (pin "128") (pinfunction "PG13/FSMC_A24/U6_CTS/ETH_MII_TXD0/ETH_RMII_TXD0_128") (pintype "passive"))
    )
    (net (code "30") (name "/DJ2_KC3") (class "Default")
      (node (ref "P7") (pin "15") (pinfunction "15_15") (pintype "passive"))
      (node (ref "U1") (pin "129") (pinfunction "PG14/FSMC_A25/U6_TX/ETH_MII_TXD1/ETH_RMII_TXD1_129") (pintype "passive"))
    )
    (net (code "31") (name "/DJ3_KC1") (class "Default")
      (node (ref "P6") (pin "8") (pinfunction "8_8") (pintype "passive"))
      (node (ref "U1") (pin "12") (pinfunction "PF2/FSMC_A2/I2C2_SMBA_12") (pintype "passive"))
    )
    (net (code "32") (name "/DJ3_KC2") (class "Default")
      (node (ref "P7") (pin "12") (pinfunction "12_12") (pintype "passive"))
      (node (ref "U1") (pin "134") (pinfunction "PB4/JNTRST/TIM3_CH1/SPI1_MISO/SPI3_MISO/I2S3ext_SD_134") (pintype "passive"))
    )
    (net (code "33") (name "/DJ3_KC3") (class "Default")
      (node (ref "P7") (pin "11") (pinfunction "11_11") (pintype "passive"))
      (node (ref "U1") (pin "137") (pinfunction "PB7/TIM4_CH2/U1_RX/FSMC_NL/I2C1_SDA/DCMI_VSYNC_137") (pintype "passive"))
    )
    (net (code "34") (name "/DJ4_KC1") (class "Default")
      (node (ref "P6") (pin "9") (pinfunction "9_9") (pintype "passive"))
      (node (ref "U1") (pin "13") (pinfunction "PF3/FSMC_A3/ADC3_IN9_13") (pintype "passive"))
    )
    (net (code "35") (name "/DJ4_KC2") (class "Default")
      (node (ref "P7") (pin "18") (pinfunction "18_18") (pintype "passive"))
      (node (ref "U1") (pin "125") (pinfunction "PG10/FSMC_NCE4_1/FSMC_NE3_125") (pintype "passive"))
    )
    (net (code "36") (name "/DJ4_KC3") (class "Default")
      (node (ref "P7") (pin "17") (pinfunction "17_17") (pintype "passive"))
      (node (ref "U1") (pin "126") (pinfunction "PG11/FSMC_NCE4_2/ETH_MII_TX_EN/ETH_RMII_TX_EN_126") (pintype "passive"))
    )
    (net (code "37") (name "/DWQ1") (class "Default")
      (node (ref "P7") (pin "9") (pinfunction "9_9") (pintype "passive"))
      (node (ref "U11") (pin "5") (pinfunction "INB+_5") (pintype "input"))
    )
    (net (code "38") (name "/DWQ1_ADC") (class "Default")
      (node (ref "U1") (pin "28") (pinfunction "PC2/SPI2_MISO/OTG_HS_ULPI_DIR/ETH_MII_TXD2/I2S2ext_SD/ADC123_IN12_28") (pintype "passive"))
      (node (ref "U11") (pin "6") (pinfunction "INB-_6") (pintype "input"))
      (node (ref "U11") (pin "7") (pinfunction "OUTB_7") (pintype "output"))
    )
    (net (code "39") (name "/DWQ2") (class "Default")
      (node (ref "P7") (pin "10") (pinfunction "10_10") (pintype "passive"))
      (node (ref "U11") (pin "10") (pinfunction "INC+_10") (pintype "input"))
    )
    (net (code "40") (name "/DWQ2_ADC") (class "Default")
      (node (ref "U1") (pin "29") (pinfunction "PC3/SPI2_MOSI/OTG_HS_ULPI_NXT/ETH_MII_TX_CLK/I2S2_SD/ADC123_IN13_29") (pintype "passive"))
      (node (ref "U11") (pin "8") (pinfunction "OUTC_8") (pintype "output"))
      (node (ref "U11") (pin "9") (pinfunction "INC-_9") (pintype "input"))
    )
    (net (code "41") (name "/F_CS") (class "Default")
      (node (ref "U1") (pin "73") (pinfunction "PB12/SPI2_NSS/TIM1_BKIN/U3_CK/CAN2_RX/I2C2_SMBA/OTG_HS_ULPI_D5/OTG_HS_ID/ETH_MII_TXD0/ETH_RMII_TXD0/I2S2_WS_73") (pintype "passive"))
      (node (ref "U9") (pin "1") (pinfunction "~{CS}_1") (pintype "passive"))
    )
    (net (code "42") (name "/IIC_SCL") (class "Default")
      (node (ref "U6") (pin "47") (pinfunction "IIC_SCL_47") (pintype "passive"))
    )
    (net (code "43") (name "/IIC_SDA") (class "Default")
      (node (ref "U6") (pin "48") (pinfunction "IIC_SDA_48") (pintype "passive"))
    )
    (net (code "44") (name "/INPUT_1") (class "Default")
      (node (ref "P6") (pin "3") (pinfunction "3_3") (pintype "passive"))
      (node (ref "U1") (pin "3") (pinfunction "PE4/TRACED1/FSMC_A20/DCMI_D4_3") (pintype "passive"))
    )
    (net (code "45") (name "/INPUT_2") (class "Default")
      (node (ref "P6") (pin "4") (pinfunction "4_4") (pintype "passive"))
      (node (ref "U1") (pin "4") (pinfunction "PE5/TRACED2/FSMC_A21/TIM9_CH1/DCMI_D6_4") (pintype "passive"))
    )
    (net (code "46") (name "/INPUT_3") (class "Default")
      (node (ref "P6") (pin "5") (pinfunction "5_5") (pintype "passive"))
      (node (ref "U1") (pin "5") (pinfunction "PE6/TRACED3/FSMC_A22/TIM9_CH2/DCMI_D7_5") (pintype "passive"))
    )
    (net (code "47") (name "/INPUT_4") (class "Default")
      (node (ref "P6") (pin "10") (pinfunction "10_10") (pintype "passive"))
      (node (ref "U1") (pin "14") (pinfunction "PF4/FSMC_A4/ADC3_IN14_14") (pintype "passive"))
    )
    (net (code "48") (name "/INPUT_5") (class "Default")
      (node (ref "P6") (pin "11") (pinfunction "11_11") (pintype "passive"))
      (node (ref "U1") (pin "15") (pinfunction "PF5/FSMC_A5/ADC3_IN15_15") (pintype "passive"))
    )
    (net (code "49") (name "/INPUT_6") (class "Default")
      (node (ref "P6") (pin "12") (pinfunction "12_12") (pintype "passive"))
      (node (ref "U1") (pin "18") (pinfunction "PF6/TIM10_CH1/FSMC_NIORD/ADC3_IN4_18") (pintype "passive"))
    )
    (net (code "50") (name "/INPUT_7") (class "Default")
      (node (ref "P6") (pin "13") (pinfunction "13_13") (pintype "passive"))
      (node (ref "U1") (pin "19") (pinfunction "PF7/TIM11_CH1/FSMC_NREG/ADC3_IN5_19") (pintype "passive"))
    )
    (net (code "51") (name "/INPUT_8") (class "Default")
      (node (ref "P6") (pin "14") (pinfunction "14_14") (pintype "passive"))
      (node (ref "U1") (pin "20") (pinfunction "PF8/TIM13_CH1/FSMC_NIOWR/ADC3_IN6_20") (pintype "passive"))
    )
    (net (code "52") (name "/INPUT_9") (class "Default")
      (node (ref "P6") (pin "15") (pinfunction "15_15") (pintype "passive"))
      (node (ref "U1") (pin "21") (pinfunction "PF9/TIM14_CH1/FSMC_CD/ADC3_IN7_21") (pintype "passive"))
    )
    (net (code "53") (name "/INPUT_10") (class "Default")
      (node (ref "P6") (pin "16") (pinfunction "16_16") (pintype "passive"))
      (node (ref "U1") (pin "22") (pinfunction "PF10/FSMC_INTR/ADC3_IN8_22") (pintype "passive"))
    )
    (net (code "54") (name "/INPUT_11") (class "Default")
      (node (ref "P6") (pin "17") (pinfunction "17_17") (pintype "passive"))
      (node (ref "U1") (pin "40") (pinfunction "PA4/SPI1_NSS/U2_CK/DCMI_HSYNC/OTG_HS_SOF/I2S3_WS/DAC1_OUT/ADC12_IN4_40") (pintype "passive"))
    )
    (net (code "55") (name "/INPUT_12") (class "Default")
      (node (ref "P6") (pin "18") (pinfunction "18_18") (pintype "passive"))
      (node (ref "U1") (pin "41") (pinfunction "PA5/SPI1_SCK/OTG_HS_ULPI_CK/TIM2_CH1_ETR/TIM8_CH1N/DAC2_OUT/ADC12_IN5_41") (pintype "passive"))
    )
    (net (code "56") (name "/INPUT_13") (class "Default")
      (node (ref "P6") (pin "19") (pinfunction "19_19") (pintype "passive"))
      (node (ref "U1") (pin "42") (pinfunction "PA6/SPI1_MISO/TIM1_BKIN/TIM3_CH1/TIM8_BKIN/TIM13_CH1/DCMI_PIXCLK/ADC12_IN6_42") (pintype "passive"))
    )
    (net (code "57") (name "/INPUT_14") (class "Default")
      (node (ref "P6") (pin "20") (pinfunction "20_20") (pintype "passive"))
      (node (ref "U1") (pin "43") (pinfunction "PA7/SPI1_MOSI/TIM1_CH1N/TIM3_CH2/TIM8_CH1N/TIM14_CH1/ETH_MII_RX_DV/ETH_RMII_CRS_DV/ADC12_IN7_43") (pintype "passive"))
    )
    (net (code "58") (name "/INPUT_15") (class "Default")
      (node (ref "U1") (pin "50") (pinfunction "PF12/FSMC_A6_50") (pintype "passive"))
    )
    (net (code "59") (name "/INPUT_16") (class "Default")
      (node (ref "U1") (pin "53") (pinfunction "PF13/FSMC_A7_53") (pintype "passive"))
    )
    (net (code "60") (name "/INPUT_17") (class "Default")
      (node (ref "P6") (pin "24") (pinfunction "24_24") (pintype "passive"))
      (node (ref "U1") (pin "54") (pinfunction "PF14/FSMC_A8_54") (pintype "passive"))
    )
    (net (code "61") (name "/INPUT_18") (class "Default")
      (node (ref "P6") (pin "25") (pinfunction "25_25") (pintype "passive"))
      (node (ref "U1") (pin "55") (pinfunction "PF15/FSMC_A9_55") (pintype "passive"))
    )
    (net (code "62") (name "/INPUT_19") (class "Default")
      (node (ref "P6") (pin "30") (pinfunction "30_30") (pintype "passive"))
      (node (ref "U1") (pin "60") (pinfunction "PE9/FSMC_D6/TIM1_CH1_60") (pintype "passive"))
    )
    (net (code "63") (name "/INPUT_20") (class "Default")
      (node (ref "P6") (pin "31") (pinfunction "31_31") (pintype "passive"))
      (node (ref "U1") (pin "63") (pinfunction "PE10/FSMC_D7/TIM1_CH2N_63") (pintype "passive"))
    )
    (net (code "64") (name "/INPUT_21") (class "Default")
      (node (ref "P6") (pin "32") (pinfunction "32_32") (pintype "passive"))
      (node (ref "U1") (pin "64") (pinfunction "PE11/FSMC_D8/TIM1_CH2_64") (pintype "passive"))
    )
    (net (code "65") (name "/INPUT_22") (class "Default")
      (node (ref "P6") (pin "33") (pinfunction "33_33") (pintype "passive"))
      (node (ref "U1") (pin "66") (pinfunction "PE13/FSMC_D10/TIM1_CH3_66") (pintype "passive"))
    )
    (net (code "66") (name "/INPUT_23") (class "Default")
      (node (ref "P6") (pin "34") (pinfunction "34_34") (pintype "passive"))
      (node (ref "U1") (pin "67") (pinfunction "PE14/FSMC_D11/TIM1_CH4_67") (pintype "passive"))
    )
    (net (code "67") (name "/INPUT_24") (class "Default")
      (node (ref "P6") (pin "35") (pinfunction "35_35") (pintype "passive"))
      (node (ref "U1") (pin "68") (pinfunction "PE15/FSMC_D12/TIM1_BKIN_68") (pintype "passive"))
    )
    (net (code "68") (name "/LDAC") (class "Default")
      (node (ref "P6") (pin "29") (pinfunction "29_29") (pintype "passive"))
      (node (ref "U1") (pin "59") (pinfunction "PE8/FSMC_D5/TIM1_CH1N_59") (pintype "passive"))
    )
    (net (code "69") (name "/LED1") (class "Default")
      (node (ref "D1") (pin "K") (pinfunction "K_K") (pintype "passive"))
      (node (ref "U1") (pin "139") (pinfunction "PB8/TIM4_CH3/TIM10_CH1/CAN1_RX/SDIO_D4/ETH_MII_TXD3/I2C1_SCL/DCMI_D6_139") (pintype "passive"))
    )
    (net (code "70") (name "/LED2") (class "Default")
      (node (ref "D2") (pin "K") (pinfunction "K_K") (pintype "passive"))
      (node (ref "U1") (pin "140") (pinfunction "PB9/TIM4_CH4/TIM11_CH1/CAN1_TX/SDIO_D5/SPI2_NSS/I2C1_SDA/DCMI_D7/I2S2_WS_140") (pintype "passive"))
    )
    (net (code "71") (name "/LED3") (class "Default")
      (node (ref "D4") (pin "K") (pinfunction "K_K") (pintype "passive"))
      (node (ref "U1") (pin "141") (pinfunction "PE0/TIM4_ETR/FSMC_NBL0/DCMI_D2_141") (pintype "passive"))
    )
    (net (code "72") (name "/LED4") (class "Default")
      (node (ref "D5") (pin "K") (pinfunction "K_K") (pintype "passive"))
      (node (ref "U1") (pin "142") (pinfunction "PE1/FSMC_NBL1/DCMI_D3_142") (pintype "passive"))
    )
    (net (code "73") (name "/LOAD") (class "Default")
      (node (ref "P6") (pin "28") (pinfunction "28_28") (pintype "passive"))
      (node (ref "U1") (pin "58") (pinfunction "PE7/FSMC_D4/TIM1_ETR_58") (pintype "passive"))
    )
    (net (code "74") (name "/MIC_BIAS") (class "Default")
      (node (ref "C68") (pin "1") (pinfunction "1_1") (pintype "passive"))
      (node (ref "U6") (pin "12") (pinfunction "MIC_Bias_12") (pintype "passive"))
    )
    (net (code "75") (name "/MIC_N") (class "Default")
      (node (ref "U6") (pin "13") (pinfunction "MIC_N_13") (pintype "passive"))
    )
    (net (code "76") (name "/MIC_P") (class "Default")
      (node (ref "U6") (pin "15") (pinfunction "MIC_P_15") (pintype "passive"))
    )
    (net (code "77") (name "/PA0_RS485_TX1") (class "Default")
      (node (ref "U1") (pin "34") (pinfunction "PA0-WKUP/U2_CTS/U4_TX/ETH_MII_CRS/TIM2_CH1_ETR/TIM5_CH1/TIM8_ETR/ADC123_IN0_34") (pintype "passive"))
      (node (ref "U10") (pin "4") (pinfunction "DI_4") (pintype "input"))
    )
    (net (code "78") (name "/PA1_RS485_RX1") (class "Default")
      (node (ref "U1") (pin "35") (pinfunction "PA1/U2_RTS/U4_RX/ETH_RMII_REF_CLK/ETH_MII_RX_CLK/TIM2_CH2/TIM5_CH2/ADC123_IN1_35") (pintype "passive"))
      (node (ref "U10") (pin "1") (pinfunction "RO_1") (pintype "output"))
    )
    (net (code "79") (name "/PA2_RS485_RE1") (class "Default")
      (node (ref "U1") (pin "36") (pinfunction "PA2/U2_TX/TIM2_CH3/TIM5_CH3/TIM9_CH1/ETH_MDIO/ADC123_IN2_36") (pintype "passive"))
      (node (ref "U10") (pin "2") (pinfunction "~{RE}_2") (pintype "input"))
      (node (ref "U10") (pin "3") (pinfunction "DE_3") (pintype "input"))
    )
    (net (code "80") (name "/PA9_U1_TX") (class "Default")
      (node (ref "R17") (pin "2") (pinfunction "2_2") (pintype "passive"))
      (node (ref "U1") (pin "101") (pinfunction "PA9/TIM1_CH2/U1_TX/I2C3_SMBA/OTG_FS_VBUS/DCMI_D0_101") (pintype "passive"))
      (node (ref "U6") (pin "39") (pinfunction "RXD_39") (pintype "passive"))
    )
    (net (code "81") (name "/PA10_U1_RX") (class "Default")
      (node (ref "R16") (pin "1") (pinfunction "1_1") (pintype "passive"))
      (node (ref "U1") (pin "102") (pinfunction "PA10/TIM1_CH3/U1_RX/OTG_FS_ID/DCMI_D1_102") (pintype "passive"))
      (node (ref "U6") (pin "41") (pinfunction "TXD_41") (pintype "passive"))
    )
    (net (code "82") (name "/PA13-JTMS") (class "Default")
      (node (ref "P2") (pin "3") (pinfunction "3_3") (pintype "passive"))
      (node (ref "R11") (pin "2") (pinfunction "2_2") (pintype "passive"))
      (node (ref "U1") (pin "105") (pinfunction "PA13/JTMS_SWDIO_105") (pintype "passive"))
    )
    (net (code "83") (name "/PA14-JTCK") (class "Default")
      (node (ref "P2") (pin "4") (pinfunction "4_4") (pintype "passive"))
      (node (ref "R10") (pin "2") (pinfunction "2_2") (pintype "passive"))
      (node (ref "U1") (pin "109") (pinfunction "PA14/JTCK_SWCLK_109") (pintype "passive"))
    )
    (net (code "84") (name "/PC6_U6_TX") (class "Default")
      (node (ref "P1") (pin "1") (pinfunction "1_1") (pintype "passive"))
      (node (ref "U1") (pin "96") (pinfunction "PC6/TIM3_CH1/TIM8_CH1/U6_TX/SDIO_D6/DCMI_D0/I2S2_MCK_96") (pintype "passive"))
    )
    (net (code "85") (name "/PC7_U6_RX") (class "Default")
      (node (ref "P1") (pin "8") (pinfunction "8_8") (pintype "passive"))
      (node (ref "U1") (pin "97") (pinfunction "PC7/TIM3_CH2/TIM8_CH2/U6_RX/SDIO_D7/DCMI_D1/I2S3_MCK_97") (pintype "passive"))
    )
    (net (code "86") (name "/PC8_SDIO_0") (class "Default")
      (node (ref "U1") (pin "98") (pinfunction "PC8/TIM3_CH3/TIM8_CH3/U6_CK/SDIO_D0/DCMI_D2_98") (pintype "passive"))
    )
    (net (code "87") (name "/PC9_SDIO_1") (class "Default")
      (node (ref "U1") (pin "99") (pinfunction "PC9/TIM3_CH4/TIM8_CH4/I2C3_SDA/SDIO_D1/DCMI_D3/MCO2/I2S_CKIN_99") (pintype "passive"))
    )
    (net (code "88") (name "/PC10_SDIO_2") (class "Default")
      (node (ref "U1") (pin "111") (pinfunction "PC10/SPI3_SCK/U3_TX/U4_TX/SDIO_D2/DCMI_D8/I2S3_CK_111") (pintype "passive"))
    )
    (net (code "89") (name "/PC11_SDIO_3") (class "Default")
      (node (ref "U1") (pin "112") (pinfunction "PC11/SPI3_MISO/U3_RX/U4_RX/SDIO_D3/DCMI_D4/I2S3ext_SD_112") (pintype "passive"))
    )
    (net (code "90") (name "/PC12_SDIO_CK") (class "Default")
      (node (ref "U1") (pin "113") (pinfunction "PC12/SPI3_MOSI/U3_CK/U5_TX/SDIO_CK/DCMI_D9/I2S3_SD_113") (pintype "passive"))
    )
    (net (code "91") (name "/PD2_SDIO_CMD") (class "Default")
      (node (ref "U1") (pin "116") (pinfunction "PD2/TIM3_ETR/U5_RX/SDIO_CMD/DCMI_D11_116") (pintype "passive"))
    )
    (net (code "92") (name "/PD5_U2_TX") (class "Default")
      (node (ref "U1") (pin "119") (pinfunction "PD5/FSMC_NWE/U2_TX_119") (pintype "passive"))
      (node (ref "U7") (pin "11") (pinfunction "DIN1_11") (pintype "passive"))
    )
    (net (code "93") (name "/PD6_U2_RX") (class "Default")
      (node (ref "U1") (pin "122") (pinfunction "PD6/FSMC_NWAIT/U2_RX_122") (pintype "passive"))
      (node (ref "U7") (pin "12") (pinfunction "ROUT1_12") (pintype "passive"))
    )
    (net (code "94") (name "/POWER_ADC") (class "Default")
      (node (ref "U1") (pin "27") (pinfunction "PC1/ETH_MDC/ADC123_IN11_27") (pintype "passive"))
      (node (ref "U11") (pin "1") (pinfunction "OUTA_1") (pintype "output"))
      (node (ref "U11") (pin "2") (pinfunction "INA-_2") (pintype "input"))
    )
    (net (code "95") (name "/PWM1") (class "Default")
      (node (ref "P7") (pin "30") (pinfunction "30_30") (pintype "passive"))
      (node (ref "U1") (pin "81") (pinfunction "PD12/FSMC_A17/FSMC_ALE/TIM4_CH1/U3_RTS_81") (pintype "passive"))
    )
    (net (code "96") (name "/PWM2") (class "Default")
      (node (ref "P7") (pin "29") (pinfunction "29_29") (pintype "passive"))
      (node (ref "U1") (pin "82") (pinfunction "PD13/FSMC_A18/TIM4_CH2_82") (pintype "passive"))
    )
    (net (code "97") (name "/PWM3") (class "Default")
      (node (ref "P7") (pin "28") (pinfunction "28_28") (pintype "passive"))
      (node (ref "U1") (pin "85") (pinfunction "PD14/FSMC_D0/TIM4_CH3_85") (pintype "passive"))
    )
    (net (code "98") (name "/PWM4") (class "Default")
      (node (ref "P7") (pin "27") (pinfunction "27_27") (pintype "passive"))
      (node (ref "U1") (pin "86") (pinfunction "PD15/FSMC_D1/TIM4_CH4_86") (pintype "passive"))
    )
    (net (code "99") (name "/QYG_KC1") (class "Default")
      (node (ref "P6") (pin "36") (pinfunction "36_36") (pintype "passive"))
      (node (ref "U1") (pin "69") (pinfunction "PB10/SPI2_SCK/TIM2_CH3/U3_TX/I2C2_SCL/OTG_HS_ULPI_D3/I2S2_CK_69") (pintype "passive"))
    )
    (net (code "100") (name "/RDY") (class "Default")
      (node (ref "D11") (pin "K") (pinfunction "K_K") (pintype "passive"))
      (node (ref "R26") (pin "2") (pinfunction "2_2") (pintype "passive"))
      (node (ref "U6") (pin "40") (pinfunction "RDY_40") (pintype "passive"))
    )
    (net (code "101") (name "/RESET") (class "Default")
      (node (ref "C1") (pin "1") (pintype "passive"))
      (node (ref "R4") (pin "1") (pintype "passive"))
      (node (ref "RESET1") (pin "1") (pinfunction "1_1") (pintype "passive"))
      (node (ref "U1") (pin "25") (pinfunction "NRST_25") (pintype "passive"))
    )
    (net (code "102") (name "/RESET_YY") (class "Default")
      (node (ref "C82") (pin "1") (pinfunction "1_1") (pintype "passive"))
      (node (ref "R27") (pin "2") (pinfunction "2_2") (pintype "passive"))
      (node (ref "U6") (pin "28") (pinfunction "RESET_28") (pintype "passive"))
    )
    (net (code "103") (name "/RS485_1A") (class "Default")
      (node (ref "P7") (pin "7") (pinfunction "7_7") (pintype "passive"))
      (node (ref "R32") (pin "2") (pintype "passive"))
      (node (ref "R33") (pin "1") (pintype "passive"))
      (node (ref "U10") (pin "6") (pinfunction "A_6") (pintype "bidirectional"))
    )
    (net (code "104") (name "/RS485_1B") (class "Default")
      (node (ref "P7") (pin "8") (pinfunction "8_8") (pintype "passive"))
      (node (ref "R33") (pin "2") (pintype "passive"))
      (node (ref "R34") (pin "1") (pintype "passive"))
      (node (ref "U10") (pin "7") (pinfunction "~{B}_7") (pintype "bidirectional"))
    )
    (net (code "105") (name "/SPI2_MISO") (class "Default")
      (node (ref "U1") (pin "75") (pinfunction "PB14/SPI2_MISO/TIM1_CH2N/TIM8_CH2N/TIM12_CH1/U3_RTS/OTG_HS_DM/I2S2ext_SD_75") (pintype "passive"))
      (node (ref "U9") (pin "2") (pinfunction "DO_2") (pintype "passive"))
    )
    (net (code "106") (name "/SPI2_MOSI") (class "Default")
      (node (ref "U1") (pin "76") (pinfunction "PB15/SPI2_MOSI/TIM1_CH3N/TIM8_CH3N/TIM12_CH2/OTG_HS_DP/I2S2_SD_76") (pintype "passive"))
      (node (ref "U9") (pin "5") (pinfunction "DI_5") (pintype "passive"))
    )
    (net (code "107") (name "/SPI2_SCK") (class "Default")
      (node (ref "U1") (pin "74") (pinfunction "PB13/SPI2_SCK/TIM1_CH1N/U3_CTS/CAN2_TX/OTG_HS_ULPI_D6/OTG_HS_VBUS/ETH_MII_TXD1/ETH_RMII_TXD1/I2S2_CK_74") (pintype "passive"))
      (node (ref "U9") (pin "6") (pinfunction "CLK_6") (pintype "passive"))
    )
    (net (code "108") (name "/SPI_CLK") (class "Default")
      (node (ref "U6") (pin "42") (pinfunction "SPI_CLK_42") (pintype "passive"))
    )
    (net (code "109") (name "/SPI_CS") (class "Default")
      (node (ref "U6") (pin "43") (pinfunction "SPI_SSEL_43") (pintype "passive"))
    )
    (net (code "110") (name "/SPI_MISO") (class "Default")
      (node (ref "U6") (pin "45") (pinfunction "SPI_SO_45") (pintype "passive"))
    )
    (net (code "111") (name "/SPI_MOSI") (class "Default")
      (node (ref "U6") (pin "44") (pinfunction "SPI_SI_44") (pintype "passive"))
    )
    (net (code "112") (name "/SSD_KC1") (class "Default")
      (node (ref "P7") (pin "24") (pinfunction "24_24") (pintype "passive"))
      (node (ref "U1") (pin "100") (pinfunction "PA8/TIM1_CH1/U1_CK/I2C3_SCL/MCO1/OTG_FS_SOF_100") (pintype "passive"))
    )
    (net (code "113") (name "/SSD_KC2") (class "Default")
      (node (ref "P7") (pin "23") (pinfunction "23_23") (pintype "passive"))
      (node (ref "U1") (pin "110") (pinfunction "PA15/JTDI/SPI1_NSS/SPI3_NSS/TIM2_CH1_ETR/I2S3_WS_110") (pintype "passive"))
    )
    (net (code "114") (name "/SSD_KC3") (class "Default")
      (node (ref "P7") (pin "22") (pinfunction "22_22") (pintype "passive"))
      (node (ref "U1") (pin "114") (pinfunction "PD0/FSMC_D2/CAN1_RX_114") (pintype "passive"))
    )
    (net (code "115") (name "/SpeekL+") (class "Default")
      (node (ref "C81") (pin "2") (pinfunction "2_2") (pintype "passive"))
      (node (ref "FB5") (pin "2") (pinfunction "2_2") (pintype "passive"))
    )
    (net (code "116") (name "/SpeekL-") (class "Default")
      (node (ref "C80") (pin "2") (pinfunction "2_2") (pintype "passive"))
      (node (ref "FB4") (pin "1") (pinfunction "1_1") (pintype "passive"))
    )
    (net (code "117") (name "/SpeekR+") (class "Default")
      (node (ref "C17") (pin "2") (pinfunction "2_2") (pintype "passive"))
      (node (ref "FB2") (pin "2") (pinfunction "2_2") (pintype "passive"))
      (node (ref "P7") (pin "6") (pinfunction "6_6") (pintype "passive"))
    )
    (net (code "118") (name "/SpeekR-") (class "Default")
      (node (ref "C16") (pin "2") (pinfunction "2_2") (pintype "passive"))
      (node (ref "FB1") (pin "1") (pinfunction "1_1") (pintype "passive"))
      (node (ref "P7") (pin "5") (pinfunction "5_5") (pintype "passive"))
    )
    (net (code "119") (name "/TXX_KC1") (class "Default")
      (node (ref "P6") (pin "21") (pinfunction "21_21") (pintype "passive"))
      (node (ref "U1") (pin "44") (pinfunction "PC4/ETH_MII_RXD0/ETH_RMII_RXD0/ADC12_IN14_44") (pintype "passive"))
    )
    (net (code "120") (name "/TXX_KC2") (class "Default")
      (node (ref "P6") (pin "22") (pinfunction "22_22") (pintype "passive"))
      (node (ref "U1") (pin "45") (pinfunction "PC5/ETH_MII_RXD1/ETH_RMII_RXD1/ADC12_IN15_45") (pintype "passive"))
    )
    (net (code "121") (name "/TXX_KC3") (class "Default")
      (node (ref "P6") (pin "23") (pinfunction "23_23") (pintype "passive"))
      (node (ref "U1") (pin "46") (pinfunction "PB0/TIM1_CH2N/TIM3_CH3/TIM8_CH2N/OTG_HS_ULPI_D1/ETH_MII_RXD2/ADC12_IN8_46") (pintype "passive"))
    )
    (net (code "122") (name "/U2_RX") (class "Default")
      (node (ref "P7") (pin "3") (pinfunction "3_3") (pintype "passive"))
      (node (ref "U7") (pin "13") (pinfunction "RIN1_13") (pintype "passive"))
    )
    (net (code "123") (name "/U2_TX") (class "Default")
      (node (ref "P7") (pin "4") (pinfunction "4_4") (pintype "passive"))
      (node (ref "U7") (pin "14") (pinfunction "DOUT1_14") (pintype "passive"))
    )
    (net (code "124") (name "/U3_RX") (class "Default")
      (node (ref "P3") (pin "4") (pinfunction "4_4") (pintype "passive"))
      (node (ref "U1") (pin "78") (pinfunction "PD9/FSMC_D14/U3_RX_78") (pintype "passive"))
    )
    (net (code "125") (name "/U3_TX") (class "Default")
      (node (ref "P3") (pin "5") (pinfunction "5_5") (pintype "passive"))
      (node (ref "U1") (pin "77") (pinfunction "PD8/FSMC_D13/U3_TX_77") (pintype "passive"))
    )
    (net (code "126") (name "/VBAT") (class "Default")
      (node (ref "U1") (pin "6") (pinfunction "VBAT_6") (pintype "passive"))
    )
    (net (code "127") (name "/VCC_T") (class "Default")
      (node (ref "K1") (pin "2") (pinfunction "TAP1_2") (pintype "passive"))
      (node (ref "P7") (pin "31") (pinfunction "31_31") (pintype "passive"))
      (node (ref "U3") (pin "3") (pinfunction "Vin_3") (pintype "passive"))
      (node (ref "U8") (pin "3") (pinfunction "Vin_3") (pintype "passive"))
    )
    (net (code "128") (name "3.3V") (class "Default")
      (node (ref "C6") (pin "1") (pinfunction "VCC_1") (pintype "passive"))
      (node (ref "C7") (pin "2") (pintype "passive"))
      (node (ref "P1") (pin "5") (pinfunction "5_5") (pintype "passive"))
      (node (ref "P1") (pin "7") (pinfunction "7_7") (pintype "passive"))
      (node (ref "P3") (pin "2") (pinfunction "2_2") (pintype "passive"))
      (node (ref "R13") (pin "1") (pintype "passive"))
      (node (ref "U3") (pin "2") (pinfunction "Vout_2") (pintype "passive"))
    )
    (net (code "129") (name "AVCC_12") (class "Default")
      (node (ref "C12") (pin "1") (pinfunction "1_1") (pintype "passive"))
      (node (ref "C15") (pin "1") (pinfunction "1_1") (pintype "passive"))
      (node (ref "C35") (pin "1") (pinfunction "1_1") (pintype "passive"))
      (node (ref "C45") (pin "1") (pinfunction "1_1") (pintype "passive"))
      (node (ref "C46") (pin "1") (pinfunction "1_1") (pintype "passive"))
      (node (ref "C47") (pin "1") (pinfunction "1_1") (pintype "passive"))
      (node (ref "C72") (pin "1") (pinfunction "1_1") (pintype "passive"))
      (node (ref "C73") (pin "1") (pinfunction "1_1") (pintype "passive"))
      (node (ref "C74") (pin "1") (pinfunction "1_1") (pintype "passive"))
      (node (ref "C75") (pin "1") (pinfunction "1_1") (pintype "passive"))
      (node (ref "D10") (pin "2") (pinfunction "K_2") (pintype "passive"))
      (node (ref "D9") (pin "2") (pinfunction "K_2") (pintype "passive"))
      (node (ref "U12") (pin "12") (pinfunction "PVCCL_12") (pintype "passive"))
      (node (ref "U12") (pin "19") (pinfunction "PVCCL_19") (pintype "passive"))
      (node (ref "U12") (pin "26") (pinfunction "AVCC_26") (pintype "passive"))
      (node (ref "U12") (pin "29") (pinfunction "~{SD}_29") (pintype "passive"))
      (node (ref "U12") (pin "32") (pinfunction "PVCCR_32") (pintype "passive"))
      (node (ref "U12") (pin "39") (pinfunction "PVCCR_39") (pintype "passive"))
    )
    (net (code "130") (name "GND") (class "Default")
      (node (ref "C1") (pin "2") (pintype "passive"))
      (node (ref "C10") (pin "1") (pintype "passive"))
      (node (ref "C12") (pin "2") (pinfunction "2_2") (pintype "passive"))
      (node (ref "C13") (pin "2") (pintype "passive"))
      (node (ref "C14") (pin "2") (pintype "passive"))
      (node (ref "C15") (pin "2") (pinfunction "2_2") (pintype "passive"))
      (node (ref "C16") (pin "1") (pinfunction "1_1") (pintype "passive"))
      (node (ref "C17") (pin "1") (pinfunction "1_1") (pintype "passive"))
      (node (ref "C19") (pin "1") (pintype "passive"))
      (node (ref "C2") (pin "2") (pintype "passive"))
      (node (ref "C20") (pin "1") (pintype "passive"))
      (node (ref "C21") (pin "1") (pintype "passive"))
      (node (ref "C22") (pin "1") (pintype "passive"))
      (node (ref "C23") (pin "1") (pintype "passive"))
      (node (ref "C24") (pin "1") (pintype "passive"))
      (node (ref "C25") (pin "1") (pintype "passive"))
      (node (ref "C26") (pin "1") (pintype "passive"))
      (node (ref "C27") (pin "1") (pintype "passive"))
      (node (ref "C28") (pin "1") (pintype "passive"))
      (node (ref "C29") (pin "1") (pintype "passive"))
      (node (ref "C3") (pin "2") (pintype "passive"))
      (node (ref "C30") (pin "1") (pintype "passive"))
      (node (ref "C32") (pin "2") (pinfunction "2_2") (pintype "passive"))
      (node (ref "C33") (pin "2") (pinfunction "2_2") (pintype "passive"))
      (node (ref "C34") (pin "2") (pinfunction "2_2") (pintype "passive"))
      (node (ref "C35") (pin "2") (pinfunction "2_2") (pintype "passive"))
      (node (ref "C36") (pin "1") (pintype "passive"))
      (node (ref "C38") (pin "2") (pinfunction "GND_2") (pintype "passive"))
      (node (ref "C4") (pin "1") (pintype "passive"))
      (node (ref "C40") (pin "1") (pintype "passive"))
      (node (ref "C42") (pin "2") (pinfunction "2_2") (pintype "passive"))
      (node (ref "C43") (pin "2") (pintype "passive"))
      (node (ref "C44") (pin "2") (pintype "passive"))
      (node (ref "C45") (pin "2") (pinfunction "2_2") (pintype "passive"))
      (node (ref "C46") (pin "2") (pinfunction "2_2") (pintype "passive"))
      (node (ref "C47") (pin "2") (pinfunction "2_2") (pintype "passive"))
      (node (ref "C48") (pin "1") (pinfunction "1_1") (pintype "passive"))
      (node (ref "C49") (pin "2") (pinfunction "2_2") (pintype "passive"))
      (node (ref "C50") (pin "2") (pinfunction "2_2") (pintype "passive"))
      (node (ref "C52") (pin "2") (pinfunction "2_2") (pintype "passive"))
      (node (ref "C53") (pin "1") (pinfunction "1_1") (pintype "passive"))
      (node (ref "C54") (pin "2") (pinfunction "2_2") (pintype "passive"))
      (node (ref "C55") (pin "2") (pinfunction "2_2") (pintype "passive"))
      (node (ref "C56") (pin "1") (pinfunction "1_1") (pintype "passive"))
      (node (ref "C57") (pin "2") (pinfunction "2_2") (pintype "passive"))
      (node (ref "C58") (pin "2") (pinfunction "2_2") (pintype "passive"))
      (node (ref "C59") (pin "2") (pinfunction "2_2") (pintype "passive"))
      (node (ref "C6") (pin "2") (pinfunction "GND_2") (pintype "passive"))
      (node (ref "C60") (pin "1") (pinfunction "1_1") (pintype "passive"))
      (node (ref "C61") (pin "2") (pinfunction "2_2") (pintype "passive"))
      (node (ref "C62") (pin "1") (pinfunction "1_1") (pintype "passive"))
      (node (ref "C63") (pin "2") (pinfunction "2_2") (pintype "passive"))
      (node (ref "C66") (pin "2") (pinfunction "2_2") (pintype "passive"))
      (node (ref "C67") (pin "1") (pinfunction "1_1") (pintype "passive"))
      (node (ref "C68") (pin "2") (pinfunction "2_2") (pintype "passive"))
      (node (ref "C69") (pin "2") (pinfunction "2_2") (pintype "passive"))
      (node (ref "C7") (pin "1") (pintype "passive"))
      (node (ref "C70") (pin "2") (pinfunction "2_2") (pintype "passive"))
      (node (ref "C71") (pin "2") (pinfunction "2_2") (pintype "passive"))
      (node (ref "C72") (pin "2") (pinfunction "2_2") (pintype "passive"))
      (node (ref "C73") (pin "2") (pinfunction "2_2") (pintype "passive"))
      (node (ref "C74") (pin "2") (pinfunction "2_2") (pintype "passive"))
      (node (ref "C75") (pin "2") (pinfunction "2_2") (pintype "passive"))
      (node (ref "C76") (pin "1") (pinfunction "1_1") (pintype "passive"))
      (node (ref "C79") (pin "1") (pinfunction "1_1") (pintype "passive"))
      (node (ref "C8") (pin "2") (pinfunction "2_2") (pintype "passive"))
      (node (ref "C80") (pin "1") (pinfunction "1_1") (pintype "passive"))
      (node (ref "C81") (pin "1") (pinfunction "1_1") (pintype "passive"))
      (node (ref "C82") (pin "2") (pinfunction "2_2") (pintype "passive"))
      (node (ref "C9") (pin "1") (pinfunction "1_1") (pintype "passive"))
      (node (ref "D12") (pin "K") (pinfunction "K_K") (pintype "passive"))
      (node (ref "D13") (pin "1") (pinfunction "A_1") (pintype "passive"))
      (node (ref "D14") (pin "1") (pinfunction "A_1") (pintype "passive"))
      (node (ref "D15") (pin "1") (pinfunction "A_1") (pintype "passive"))
      (node (ref "D16") (pin "1") (pinfunction "A_1") (pintype "passive"))
      (node (ref "D6") (pin "1") (pinfunction "A_1") (pintype "passive"))
      (node (ref "D7") (pin "1") (pinfunction "A_1") (pintype "passive"))
      (node (ref "D8") (pin "K") (pinfunction "K_K") (pintype "passive"))
      (node (ref "J3") (pin "1") (pinfunction "-VIN_1") (pintype "passive"))
      (node (ref "J3") (pin "5") (pinfunction "GND_5") (pintype "passive"))
      (node (ref "P1") (pin "4") (pinfunction "4_4") (pintype "passive"))
      (node (ref "P2") (pin "2") (pinfunction "2_2") (pintype "passive"))
      (node (ref "P3") (pin "1") (pinfunction "1_1") (pintype "passive"))
      (node (ref "P3") (pin "6") (pinfunction "6_6") (pintype "passive"))
      (node (ref "P3") (pin "7") (pinfunction "7_7") (pintype "passive"))
      (node (ref "P7") (pin "2") (pinfunction "2_2") (pintype "passive"))
      (node (ref "Q4") (pin "2") (pinfunction "E_2") (pintype "passive"))
      (node (ref "R1") (pin "2") (pintype "passive"))
      (node (ref "R10") (pin "1") (pinfunction "1_1") (pintype "passive"))
      (node (ref "R15") (pin "2") (pintype "passive"))
      (node (ref "R18") (pin "1") (pinfunction "1_1") (pintype "passive"))
      (node (ref "R19") (pin "1") (pinfunction "1_1") (pintype "passive"))
      (node (ref "R2") (pin "1") (pintype "passive"))
      (node (ref "R21") (pin "2") (pinfunction "2_2") (pintype "passive"))
      (node (ref "R24") (pin "1") (pinfunction "1_1") (pintype "passive"))
      (node (ref "R34") (pin "2") (pintype "passive"))
      (node (ref "R36") (pin "1") (pinfunction "1_1") (pintype "passive"))
      (node (ref "R41") (pin "1") (pintype "passive"))
      (node (ref "R6") (pin "2") (pintype "passive"))
      (node (ref "R7") (pin "2") (pintype "passive"))
      (node (ref "R8") (pin "2") (pintype "passive"))
      (node (ref "RESET1") (pin "2") (pinfunction "2_2") (pintype "passive"))
      (node (ref "U1") (pin "107") (pinfunction "VSS_107") (pintype "passive"))
      (node (ref "U1") (pin "120") (pinfunction "VSS_120") (pintype "passive"))
      (node (ref "U1") (pin "130") (pinfunction "VSS_130") (pintype "passive"))
      (node (ref "U1") (pin "16") (pinfunction "VSS_16") (pintype "passive"))
      (node (ref "U1") (pin "31") (pinfunction "VSSA_31") (pintype "passive"))
      (node (ref "U1") (pin "38") (pinfunction "VSS_38") (pintype "passive"))
      (node (ref "U1") (pin "51") (pinfunction "VSS_51") (pintype "passive"))
      (node (ref "U1") (pin "61") (pinfunction "VSS_61") (pintype "passive"))
      (node (ref "U1") (pin "83") (pinfunction "VSS_83") (pintype "passive"))
      (node (ref "U1") (pin "94") (pinfunction "VSS_94") (pintype "passive"))
      (node (ref "U10") (pin "5") (pinfunction "GND_5") (pintype "power_in"))
      (node (ref "U11") (pin "11") (pinfunction "V-_11") (pintype "power_in"))
      (node (ref "U12") (pin "11") (pinfunction "PGNDL_11") (pintype "passive"))
      (node (ref "U12") (pin "20") (pinfunction "PGNDL_20") (pintype "passive"))
      (node (ref "U12") (pin "24") (pinfunction "AGND_24") (pintype "passive"))
      (node (ref "U12") (pin "25") (pinfunction "MUTE_25") (pintype "passive"))
      (node (ref "U12") (pin "28") (pinfunction "AGND_28") (pintype "passive"))
      (node (ref "U12") (pin "31") (pinfunction "PGNDR_31") (pintype "passive"))
      (node (ref "U12") (pin "40") (pinfunction "PGNDR_40") (pintype "passive"))
      (node (ref "U12") (pin "6") (pinfunction "REFGND_6") (pintype "passive"))
      (node (ref "U12") (pin "7") (pinfunction "AGND1_7") (pintype "passive"))
      (node (ref "U12") (pin "8") (pinfunction "~{FADE}_8") (pintype "passive"))
      (node (ref "U2") (pin "2") (pinfunction "GND_2") (pintype "passive"))
      (node (ref "U2") (pin "8") (pinfunction "RS_8") (pintype "passive"))
      (node (ref "U3") (pin "1") (pinfunction "GND_1") (pintype "passive"))
      (node (ref "U4") (pin "2") (pinfunction "GND_2") (pintype "passive"))
      (node (ref "U4") (pin "8") (pinfunction "RS_8") (pintype "passive"))
      (node (ref "U5") (pin "5") (pinfunction "GND_5") (pintype "passive"))
      (node (ref "U6") (pin "10") (pinfunction "AGND_10") (pintype "passive"))
      (node (ref "U6") (pin "14") (pinfunction "AGND_14") (pintype "passive"))
      (node (ref "U6") (pin "25") (pinfunction "GND_25") (pintype "passive"))
      (node (ref "U6") (pin "37") (pinfunction "GND_37") (pintype "passive"))
      (node (ref "U6") (pin "4") (pinfunction "GND_4") (pintype "passive"))
      (node (ref "U6") (pin "52") (pinfunction "GND_52") (pintype "passive"))
      (node (ref "U6") (pin "64") (pinfunction "GND_64") (pintype "passive"))
      (node (ref "U7") (pin "15") (pinfunction "GND_15") (pintype "passive"))
      (node (ref "U8") (pin "1") (pinfunction "GND_1") (pintype "passive"))
      (node (ref "U9") (pin "4") (pinfunction "GND_4") (pintype "passive"))
    )
    (net (code "131") (name "Net-(BEEP1-G)") (class "Default")
      (node (ref "BEEP1") (pin "2") (pinfunction "G_2") (pintype "passive"))
      (node (ref "Q4") (pin "3") (pinfunction "C_3") (pintype "passive"))
    )
    (net (code "132") (name "Net-(C11-Pad1)") (class "Default")
      (node (ref "C11") (pin "1") (pinfunction "1_1") (pintype "passive"))
      (node (ref "R15") (pin "1") (pintype "passive"))
    )
    (net (code "133") (name "Net-(C18-Pad1)") (class "Default")
      (node (ref "C18") (pin "1") (pinfunction "1_1") (pintype "passive"))
      (node (ref "FB1") (pin "2") (pinfunction "2_2") (pintype "passive"))
      (node (ref "U12") (pin "37") (pinfunction "ROUTN_37") (pintype "passive"))
      (node (ref "U12") (pin "38") (pinfunction "ROUTN_38") (pintype "passive"))
    )
    (net (code "134") (name "Net-(C31-Pad2)") (class "Default")
      (node (ref "C31") (pin "2") (pinfunction "2_2") (pintype "passive"))
      (node (ref "FB2") (pin "1") (pinfunction "1_1") (pintype "passive"))
      (node (ref "U12") (pin "33") (pinfunction "ROUTP_33") (pintype "passive"))
      (node (ref "U12") (pin "34") (pinfunction "ROUTP_34") (pintype "passive"))
    )
    (net (code "135") (name "Net-(C77-Pad2)") (class "Default")
      (node (ref "C77") (pin "2") (pinfunction "2_2") (pintype "passive"))
      (node (ref "FB4") (pin "2") (pinfunction "2_2") (pintype "passive"))
      (node (ref "U12") (pin "13") (pinfunction "LOUTN_13") (pintype "passive"))
      (node (ref "U12") (pin "14") (pinfunction "LOUTN_14") (pintype "passive"))
    )
    (net (code "136") (name "Net-(C78-Pad2)") (class "Default")
      (node (ref "C78") (pin "2") (pinfunction "2_2") (pintype "passive"))
      (node (ref "FB5") (pin "1") (pinfunction "1_1") (pintype "passive"))
      (node (ref "U12") (pin "17") (pinfunction "LOUTP_17") (pintype "passive"))
      (node (ref "U12") (pin "18") (pinfunction "LOUTP_18") (pintype "passive"))
    )
    (net (code "137") (name "Net-(D1-PadA)") (class "Default")
      (node (ref "D1") (pin "A") (pinfunction "A_A") (pintype "passive"))
      (node (ref "PR1") (pin "1") (pinfunction "1_1") (pintype "passive"))
    )
    (net (code "138") (name "Net-(D2-PadA)") (class "Default")
      (node (ref "D2") (pin "A") (pinfunction "A_A") (pintype "passive"))
      (node (ref "PR1") (pin "2") (pinfunction "2_2") (pintype "passive"))
    )
    (net (code "139") (name "Net-(D3-PadA)") (class "Default")
      (node (ref "D3") (pin "A") (pinfunction "A_A") (pintype "passive"))
      (node (ref "R13") (pin "2") (pintype "passive"))
    )
    (net (code "140") (name "Net-(D4-PadA)") (class "Default")
      (node (ref "D4") (pin "A") (pinfunction "A_A") (pintype "passive"))
      (node (ref "PR1") (pin "3") (pinfunction "3_3") (pintype "passive"))
    )
    (net (code "141") (name "Net-(D5-PadA)") (class "Default")
      (node (ref "D5") (pin "A") (pinfunction "A_A") (pintype "passive"))
      (node (ref "PR1") (pin "4") (pinfunction "4_4") (pintype "passive"))
    )
    (net (code "142") (name "Net-(D7-K)") (class "Default")
      (node (ref "C5") (pin "1") (pinfunction "1_1") (pintype "passive"))
      (node (ref "D7") (pin "2") (pinfunction "K_2") (pintype "passive"))
      (node (ref "L1") (pin "1") (pinfunction "1_1") (pintype "passive"))
      (node (ref "U5") (pin "1") (pinfunction "SW_1") (pintype "passive"))
    )
    (net (code "143") (name "Net-(D8-PadA)") (class "Default")
      (node (ref "D8") (pin "A") (pinfunction "A_A") (pintype "passive"))
      (node (ref "R25") (pin "2") (pintype "passive"))
    )
    (net (code "144") (name "Net-(D11-PadA)") (class "Default")
      (node (ref "D11") (pin "A") (pinfunction "A_A") (pintype "passive"))
      (node (ref "R28") (pin "2") (pinfunction "2_2") (pintype "passive"))
    )
    (net (code "145") (name "Net-(D12-PadA)") (class "Default")
      (node (ref "D12") (pin "A") (pinfunction "A_A") (pintype "passive"))
      (node (ref "R29") (pin "2") (pintype "passive"))
    )
    (net (code "146") (name "Net-(D13-K)") (class "Default")
      (node (ref "D13") (pin "2") (pinfunction "K_2") (pintype "passive"))
      (node (ref "F1") (pin "2") (pinfunction "2_2") (pintype "passive"))
      (node (ref "R9") (pin "2") (pintype "passive"))
      (node (ref "U2") (pin "7") (pinfunction "CANH_7") (pintype "passive"))
    )
    (net (code "147") (name "Net-(D14-K)") (class "Default")
      (node (ref "D14") (pin "2") (pinfunction "K_2") (pintype "passive"))
      (node (ref "F2") (pin "2") (pinfunction "2_2") (pintype "passive"))
      (node (ref "R14") (pin "2") (pintype "passive"))
      (node (ref "U4") (pin "7") (pinfunction "CANH_7") (pintype "passive"))
    )
    (net (code "148") (name "Net-(D15-K)") (class "Default")
      (node (ref "D15") (pin "2") (pinfunction "K_2") (pintype "passive"))
      (node (ref "F3") (pin "2") (pinfunction "2_2") (pintype "passive"))
      (node (ref "R9") (pin "1") (pintype "passive"))
      (node (ref "U2") (pin "6") (pinfunction "CANL_6") (pintype "passive"))
    )
    (net (code "149") (name "Net-(D16-K)") (class "Default")
      (node (ref "D16") (pin "2") (pinfunction "K_2") (pintype "passive"))
      (node (ref "F4") (pin "2") (pinfunction "2_2") (pintype "passive"))
      (node (ref "R14") (pin "1") (pintype "passive"))
      (node (ref "U4") (pin "6") (pinfunction "CANL_6") (pintype "passive"))
    )
    (net (code "150") (name "Net-(Q4-B)") (class "Default")
      (node (ref "Q4") (pin "1") (pinfunction "B_1") (pintype "passive"))
      (node (ref "R40") (pin "2") (pintype "passive"))
      (node (ref "R41") (pin "2") (pintype "passive"))
    )
    (net (code "151") (name "Net-(U1-PDR_ON)") (class "Default")
      (node (ref "R20") (pin "1") (pintype "passive"))
      (node (ref "U1") (pin "143") (pinfunction "PDR_ON_143") (pintype "passive"))
    )
    (net (code "152") (name "Net-(U1-PH0-OSC_IN)") (class "Default")
      (node (ref "C4") (pin "2") (pintype "passive"))
      (node (ref "R12") (pin "2") (pintype "passive"))
      (node (ref "U1") (pin "23") (pinfunction "PH0-OSC_IN_23") (pintype "passive"))
      (node (ref "Y2") (pin "2") (pinfunction "OSC2_2") (pintype "passive"))
    )
    (net (code "153") (name "Net-(U1-PH1-OSC_OUT)") (class "Default")
      (node (ref "C10") (pin "2") (pintype "passive"))
      (node (ref "R12") (pin "1") (pintype "passive"))
      (node (ref "U1") (pin "24") (pinfunction "PH1-OSC_OUT_24") (pintype "passive"))
      (node (ref "Y2") (pin "1") (pinfunction "OSC1_1") (pintype "passive"))
    )
    (net (code "154") (name "Net-(U1-Vcap_1)") (class "Default")
      (node (ref "C13") (pin "1") (pintype "passive"))
      (node (ref "U1") (pin "71") (pinfunction "Vcap_1_71") (pintype "passive"))
    )
    (net (code "155") (name "Net-(U1-Vcap_2)") (class "Default")
      (node (ref "C14") (pin "1") (pintype "passive"))
      (node (ref "U1") (pin "106") (pinfunction "Vcap_2_106") (pintype "passive"))
    )
    (net (code "156") (name "Net-(U5-BST)") (class "Default")
      (node (ref "C5") (pin "2") (pinfunction "2_2") (pintype "passive"))
      (node (ref "U5") (pin "8") (pinfunction "BST_8") (pintype "passive"))
    )
    (net (code "157") (name "Net-(U5-COMP)") (class "Default")
      (node (ref "C11") (pin "2") (pinfunction "2_2") (pintype "passive"))
      (node (ref "U5") (pin "3") (pinfunction "COMP_3") (pintype "passive"))
    )
    (net (code "158") (name "Net-(U5-EN)") (class "Default")
      (node (ref "R3") (pin "2") (pintype "passive"))
      (node (ref "R7") (pin "1") (pintype "passive"))
      (node (ref "U5") (pin "2") (pinfunction "EN_2") (pintype "passive"))
    )
    (net (code "159") (name "Net-(U5-FB)") (class "Default")
      (node (ref "R5") (pin "1") (pintype "passive"))
      (node (ref "R6") (pin "1") (pintype "passive"))
      (node (ref "U5") (pin "4") (pinfunction "FB_4") (pintype "passive"))
    )
    (net (code "160") (name "Net-(U5-FREQ)") (class "Default")
      (node (ref "R8") (pin "1") (pintype "passive"))
      (node (ref "U5") (pin "6") (pinfunction "FREQ_6") (pintype "passive"))
    )
    (net (code "161") (name "Net-(U6-A1)") (class "Default")
      (node (ref "U6") (pin "53") (pinfunction "A1_53") (pintype "passive"))
      (node (ref "U6") (pin "54") (pinfunction "A2_54") (pintype "passive"))
    )
    (net (code "162") (name "Net-(U6-A3)") (class "Default")
      (node (ref "R24") (pin "2") (pinfunction "2_2") (pintype "passive"))
      (node (ref "U6") (pin "62") (pinfunction "A3_62") (pintype "passive"))
    )
    (net (code "163") (name "Net-(U6-A4)") (class "Default")
      (node (ref "R23") (pin "1") (pinfunction "1_1") (pintype "passive"))
      (node (ref "U6") (pin "29") (pinfunction "A4_29") (pintype "passive"))
    )
    (net (code "164") (name "Net-(U6-AO_N)") (class "Default")
      (node (ref "C67") (pin "2") (pinfunction "2_2") (pintype "passive"))
      (node (ref "U6") (pin "9") (pinfunction "AO_N_9") (pintype "passive"))
    )
    (net (code "165") (name "Net-(U6-AO_P)") (class "Default")
      (node (ref "C64") (pin "2") (pinfunction "2_2") (pintype "passive"))
      (node (ref "U6") (pin "8") (pinfunction "AO_P_8") (pintype "passive"))
    )
    (net (code "166") (name "Net-(U6-BAUD1)") (class "Default")
      (node (ref "R21") (pin "1") (pinfunction "1_1") (pintype "passive"))
      (node (ref "U6") (pin "56") (pinfunction "BAUD1_56") (pintype "passive"))
    )
    (net (code "167") (name "Net-(U6-BAUD2)") (class "Default")
      (node (ref "R22") (pin "1") (pinfunction "1_1") (pintype "passive"))
      (node (ref "U6") (pin "55") (pinfunction "BAUD2_55") (pintype "passive"))
    )
    (net (code "168") (name "Net-(U6-RREF)") (class "Default")
      (node (ref "R19") (pin "2") (pinfunction "2_2") (pintype "passive"))
      (node (ref "U6") (pin "3") (pinfunction "RREF_3") (pintype "passive"))
    )
    (net (code "169") (name "Net-(U6-VCM)") (class "Default")
      (node (ref "C69") (pin "1") (pinfunction "1_1") (pintype "passive"))
      (node (ref "U6") (pin "11") (pinfunction "VCM_11") (pintype "passive"))
    )
    (net (code "170") (name "Net-(U6-VREF)") (class "Default")
      (node (ref "C48") (pin "2") (pinfunction "2_2") (pintype "passive"))
      (node (ref "U6") (pin "18") (pinfunction "VREF_18") (pintype "passive"))
    )
    (net (code "171") (name "Net-(U6-XTALI)") (class "Default")
      (node (ref "C76") (pin "2") (pinfunction "2_2") (pintype "passive"))
      (node (ref "U6") (pin "26") (pinfunction "XTALI_26") (pintype "passive"))
      (node (ref "Y1") (pin "1") (pinfunction "1_1") (pintype "passive"))
    )
    (net (code "172") (name "Net-(U6-XTALO)") (class "Default")
      (node (ref "C79") (pin "2") (pinfunction "2_2") (pintype "passive"))
      (node (ref "U6") (pin "27") (pinfunction "XTALO_27") (pintype "passive"))
      (node (ref "Y1") (pin "2") (pinfunction "2_2") (pintype "passive"))
    )
    (net (code "173") (name "Net-(U7-C1+)") (class "Default")
      (node (ref "C37") (pin "1") (pinfunction "1_1") (pintype "passive"))
      (node (ref "U7") (pin "1") (pinfunction "C1+_1") (pintype "passive"))
    )
    (net (code "174") (name "Net-(U7-C1-)") (class "Default")
      (node (ref "C37") (pin "2") (pinfunction "2_2") (pintype "passive"))
      (node (ref "U7") (pin "3") (pinfunction "C1-_3") (pintype "passive"))
    )
    (net (code "175") (name "Net-(U7-C2+)") (class "Default")
      (node (ref "C41") (pin "1") (pinfunction "1_1") (pintype "passive"))
      (node (ref "U7") (pin "4") (pinfunction "C2+_4") (pintype "passive"))
    )
    (net (code "176") (name "Net-(U7-C2-)") (class "Default")
      (node (ref "C41") (pin "2") (pinfunction "2_2") (pintype "passive"))
      (node (ref "U7") (pin "5") (pinfunction "C2-_5") (pintype "passive"))
    )
    (net (code "177") (name "Net-(U7-V+)") (class "Default")
      (node (ref "C39") (pin "1") (pinfunction "1_1") (pintype "passive"))
      (node (ref "U7") (pin "2") (pinfunction "V+_2") (pintype "passive"))
    )
    (net (code "178") (name "Net-(U7-V-)") (class "Default")
      (node (ref "C42") (pin "1") (pinfunction "1_1") (pintype "passive"))
      (node (ref "U7") (pin "6") (pinfunction "V-_6") (pintype "passive"))
    )
    (net (code "179") (name "Net-(U11A-INA+)") (class "Default")
      (node (ref "R35") (pin "1") (pinfunction "1_1") (pintype "passive"))
      (node (ref "R36") (pin "2") (pinfunction "2_2") (pintype "passive"))
      (node (ref "U11") (pin "3") (pinfunction "INA+_3") (pintype "input"))
    )
    (net (code "180") (name "Net-(U12-AVDD)") (class "Default")
      (node (ref "C56") (pin "2") (pinfunction "2_2") (pintype "passive"))
      (node (ref "U12") (pin "3") (pinfunction "AVDD_3") (pintype "passive"))
      (node (ref "U12") (pin "4") (pinfunction "VREF_4") (pintype "passive"))
      (node (ref "U12") (pin "5") (pinfunction "VOLUME_5") (pintype "passive"))
    )
    (net (code "181") (name "Net-(U12-BSLN)") (class "Default")
      (node (ref "C77") (pin "1") (pinfunction "1_1") (pintype "passive"))
      (node (ref "U12") (pin "15") (pinfunction "BSLN_15") (pintype "passive"))
    )
    (net (code "182") (name "Net-(U12-BSLP)") (class "Default")
      (node (ref "C78") (pin "1") (pinfunction "1_1") (pintype "passive"))
      (node (ref "U12") (pin "16") (pinfunction "BSLP_16") (pintype "passive"))
    )
    (net (code "183") (name "Net-(U12-BSRN)") (class "Default")
      (node (ref "C18") (pin "2") (pinfunction "2_2") (pintype "passive"))
      (node (ref "U12") (pin "36") (pinfunction "BSRN_36") (pintype "passive"))
    )
    (net (code "184") (name "Net-(U12-BSRP)") (class "Default")
      (node (ref "C31") (pin "1") (pinfunction "1_1") (pintype "passive"))
      (node (ref "U12") (pin "35") (pinfunction "BSRP_35") (pintype "passive"))
    )
    (net (code "185") (name "Net-(U12-COSC)") (class "Default")
      (node (ref "C63") (pin "1") (pinfunction "1_1") (pintype "passive"))
      (node (ref "U12") (pin "22") (pinfunction "COSC_22") (pintype "passive"))
    )
    (net (code "186") (name "Net-(U12-LINN)") (class "Default")
      (node (ref "C65") (pin "2") (pinfunction "2_2") (pintype "passive"))
      (node (ref "U12") (pin "10") (pinfunction "LINN_10") (pintype "passive"))
    )
    (net (code "187") (name "Net-(U12-LINP)") (class "Default")
      (node (ref "C62") (pin "2") (pinfunction "2_2") (pintype "passive"))
      (node (ref "U12") (pin "9") (pinfunction "LINP_9") (pintype "passive"))
    )
    (net (code "188") (name "Net-(U12-RINN)") (class "Default")
      (node (ref "C51") (pin "2") (pinfunction "2_2") (pintype "passive"))
      (node (ref "U12") (pin "1") (pinfunction "RINN_1") (pintype "passive"))
    )
    (net (code "189") (name "Net-(U12-RINP)") (class "Default")
      (node (ref "C53") (pin "2") (pinfunction "2_2") (pintype "passive"))
      (node (ref "U12") (pin "2") (pinfunction "RINP_2") (pintype "passive"))
    )
    (net (code "190") (name "Net-(U12-ROSC)") (class "Default")
      (node (ref "R18") (pin "2") (pinfunction "2_2") (pintype "passive"))
      (node (ref "U12") (pin "23") (pinfunction "ROSC_23") (pintype "passive"))
    )
    (net (code "191") (name "Net-(U12-V2P5)") (class "Default")
      (node (ref "C57") (pin "1") (pinfunction "1_1") (pintype "passive"))
      (node (ref "U12") (pin "27") (pinfunction "V2P5_27") (pintype "passive"))
    )
    (net (code "192") (name "Net-(U12-VCLAMPL)") (class "Default")
      (node (ref "C66") (pin "1") (pinfunction "1_1") (pintype "passive"))
      (node (ref "U12") (pin "21") (pinfunction "VCLAMPL_21") (pintype "passive"))
    )
    (net (code "193") (name "Net-(U12-VCLAMPR)") (class "Default")
      (node (ref "C52") (pin "1") (pinfunction "1_1") (pintype "passive"))
      (node (ref "U12") (pin "30") (pinfunction "VCLAMPR_30") (pintype "passive"))
    )
    (net (code "194") (name "VCC") (class "Default")
      (node (ref "J3") (pin "3") (pinfunction "+V0_3") (pintype "passive"))
      (node (ref "K1") (pin "3") (pinfunction "I/O1_3") (pintype "passive"))
      (node (ref "U11") (pin "4") (pinfunction "V+_4") (pintype "power_in"))
    )
    (net (code "195") (name "VCC3.3") (class "Default")
      (node (ref "BEEP1") (pin "1") (pinfunction "P_1") (pintype "passive"))
      (node (ref "C19") (pin "2") (pintype "passive"))
      (node (ref "C2") (pin "1") (pintype "passive"))
      (node (ref "C20") (pin "2") (pintype "passive"))
      (node (ref "C21") (pin "2") (pintype "passive"))
      (node (ref "C22") (pin "2") (pintype "passive"))
      (node (ref "C23") (pin "2") (pintype "passive"))
      (node (ref "C24") (pin "2") (pintype "passive"))
      (node (ref "C25") (pin "2") (pintype "passive"))
      (node (ref "C26") (pin "2") (pintype "passive"))
      (node (ref "C27") (pin "2") (pintype "passive"))
      (node (ref "C28") (pin "2") (pintype "passive"))
      (node (ref "C29") (pin "2") (pintype "passive"))
      (node (ref "C3") (pin "1") (pintype "passive"))
      (node (ref "C30") (pin "2") (pintype "passive"))
      (node (ref "C36") (pin "2") (pintype "passive"))
      (node (ref "C38") (pin "1") (pinfunction "VCC_1") (pintype "passive"))
      (node (ref "C39") (pin "2") (pinfunction "2_2") (pintype "passive"))
      (node (ref "C40") (pin "2") (pintype "passive"))
      (node (ref "C43") (pin "1") (pintype "passive"))
      (node (ref "C44") (pin "1") (pintype "passive"))
      (node (ref "C70") (pin "1") (pinfunction "1_1") (pintype "passive"))
      (node (ref "C71") (pin "1") (pinfunction "1_1") (pintype "passive"))
      (node (ref "D6") (pin "2") (pinfunction "K_2") (pintype "passive"))
      (node (ref "P2") (pin "1") (pinfunction "1_1") (pintype "passive"))
      (node (ref "P7") (pin "32") (pinfunction "32_32") (pintype "passive"))
      (node (ref "PR1") (pin "5") (pinfunction "5_5") (pintype "passive"))
      (node (ref "PR1") (pin "6") (pinfunction "6_6") (pintype "passive"))
      (node (ref "PR1") (pin "7") (pinfunction "7_7") (pintype "passive"))
      (node (ref "PR1") (pin "8") (pinfunction "8_8") (pintype "passive"))
      (node (ref "R11") (pin "1") (pinfunction "1_1") (pintype "passive"))
      (node (ref "R20") (pin "2") (pintype "passive"))
      (node (ref "R25") (pin "1") (pintype "passive"))
      (node (ref "R28") (pin "1") (pinfunction "1_1") (pintype "passive"))
      (node (ref "R32") (pin "1") (pintype "passive"))
      (node (ref "R4") (pin "2") (pintype "passive"))
      (node (ref "U1") (pin "108") (pinfunction "VDD_108") (pintype "passive"))
      (node (ref "U1") (pin "121") (pinfunction "VDD_121") (pintype "passive"))
      (node (ref "U1") (pin "131") (pinfunction "VDD_131") (pintype "passive"))
      (node (ref "U1") (pin "144") (pinfunction "VDD_144") (pintype "passive"))
      (node (ref "U1") (pin "17") (pinfunction "VDD_17") (pintype "passive"))
      (node (ref "U1") (pin "30") (pinfunction "VDD_30") (pintype "passive"))
      (node (ref "U1") (pin "32") (pinfunction "Vref+_32") (pintype "passive"))
      (node (ref "U1") (pin "33") (pinfunction "VDDA_33") (pintype "passive"))
      (node (ref "U1") (pin "39") (pinfunction "VDD_39") (pintype "passive"))
      (node (ref "U1") (pin "52") (pinfunction "VDD_52") (pintype "passive"))
      (node (ref "U1") (pin "62") (pinfunction "VDD_62") (pintype "passive"))
      (node (ref "U1") (pin "72") (pinfunction "VDD_72") (pintype "passive"))
      (node (ref "U1") (pin "84") (pinfunction "VDD_84") (pintype "passive"))
      (node (ref "U1") (pin "95") (pinfunction "VDD_95") (pintype "passive"))
      (node (ref "U10") (pin "8") (pinfunction "VCC_8") (pintype "power_in"))
      (node (ref "U2") (pin "3") (pinfunction "VCC_3") (pintype "passive"))
      (node (ref "U4") (pin "3") (pinfunction "VCC_3") (pintype "passive"))
      (node (ref "U6") (pin "20") (pinfunction "PWR_IN_20") (pintype "passive"))
      (node (ref "U7") (pin "16") (pinfunction "VCC_16") (pintype "passive"))
      (node (ref "U8") (pin "2") (pinfunction "Vout_2") (pintype "passive"))
      (node (ref "U9") (pin "3") (pinfunction "~{WP}_3") (pintype "passive"))
      (node (ref "U9") (pin "7") (pinfunction "~{HOLD}_7") (pintype "passive"))
      (node (ref "U9") (pin "8") (pinfunction "VCC_8") (pintype "passive"))
    )
    (net (code "196") (name "VCC12") (class "Default")
      (node (ref "C9") (pin "2") (pinfunction "2_2") (pintype "passive"))
      (node (ref "D10") (pin "1") (pinfunction "A_1") (pintype "passive"))
      (node (ref "D9") (pin "1") (pinfunction "A_1") (pintype "passive"))
      (node (ref "L1") (pin "2") (pinfunction "2_2") (pintype "passive"))
      (node (ref "R29") (pin "1") (pintype "passive"))
      (node (ref "R5") (pin "2") (pintype "passive"))
    )
    (net (code "197") (name "VCC24") (class "Default")
      (node (ref "J3") (pin "2") (pinfunction "+VIN_2") (pintype "passive"))
      (node (ref "K1") (pin "5") (pinfunction "TAP2_5") (pintype "passive"))
      (node (ref "P7") (pin "1") (pinfunction "1_1") (pintype "passive"))
    )
    (net (code "198") (name "VCC24_T") (class "Default")
      (node (ref "C8") (pin "1") (pinfunction "1_1") (pintype "passive"))
      (node (ref "K1") (pin "6") (pinfunction "I/O2_6") (pintype "passive"))
      (node (ref "R3") (pin "1") (pintype "passive"))
      (node (ref "R35") (pin "2") (pinfunction "2_2") (pintype "passive"))
      (node (ref "U5") (pin "7") (pinfunction "VIN_7") (pintype "passive"))
    )
    (net (code "199") (name "VDD12") (class "Default")
      (node (ref "C34") (pin "1") (pinfunction "1_1") (pintype "passive"))
      (node (ref "C58") (pin "1") (pinfunction "1_1") (pintype "passive"))
      (node (ref "C59") (pin "1") (pinfunction "1_1") (pintype "passive"))
      (node (ref "U6") (pin "1") (pinfunction "VDD12_1") (pintype "passive"))
      (node (ref "U6") (pin "23") (pinfunction "VDD12_O_23") (pintype "passive"))
    )
    (net (code "200") (name "VDD33") (class "Default")
      (node (ref "C32") (pin "1") (pinfunction "1_1") (pintype "passive"))
      (node (ref "C33") (pin "1") (pinfunction "1_1") (pintype "passive"))
      (node (ref "C49") (pin "1") (pinfunction "1_1") (pintype "passive"))
      (node (ref "C50") (pin "1") (pinfunction "1_1") (pintype "passive"))
      (node (ref "FB3") (pin "2") (pinfunction "2_2") (pintype "passive"))
      (node (ref "R16") (pin "2") (pinfunction "2_2") (pintype "passive"))
      (node (ref "R17") (pin "1") (pinfunction "1_1") (pintype "passive"))
      (node (ref "R22") (pin "2") (pinfunction "2_2") (pintype "passive"))
      (node (ref "R23") (pin "2") (pinfunction "2_2") (pintype "passive"))
      (node (ref "R26") (pin "1") (pinfunction "1_1") (pintype "passive"))
      (node (ref "R27") (pin "1") (pinfunction "1_1") (pintype "passive"))
      (node (ref "U6") (pin "22") (pinfunction "VDD33_O_22") (pintype "passive"))
      (node (ref "U6") (pin "36") (pinfunction "VDD33_36") (pintype "passive"))
      (node (ref "U6") (pin "46") (pinfunction "VDD33_46") (pintype "passive"))
    )
    (net (code "201") (name "unconnected-(J3-NC-Pad4)") (class "Default")
      (node (ref "J3") (pin "4") (pinfunction "NC_4") (pintype "passive"))
    )
    (net (code "202") (name "unconnected-(K1-I{slash}O1-Pad1)") (class "Default")
      (node (ref "K1") (pin "1") (pinfunction "I/O1_1") (pintype "passive"))
    )
    (net (code "203") (name "unconnected-(K1-I{slash}O2-Pad4)") (class "Default")
      (node (ref "K1") (pin "4") (pinfunction "I/O2_4") (pintype "passive"))
    )
    (net (code "204") (name "unconnected-(P1-Pad2)") (class "Default")
      (node (ref "P1") (pin "2") (pinfunction "2_2") (pintype "passive"))
    )
    (net (code "205") (name "unconnected-(P1-Pad3)") (class "Default")
      (node (ref "P1") (pin "3") (pinfunction "3_3") (pintype "passive"))
    )
    (net (code "206") (name "unconnected-(P1-Pad6)") (class "Default")
      (node (ref "P1") (pin "6") (pinfunction "6_6") (pintype "passive"))
    )
    (net (code "207") (name "unconnected-(U1-PB1{slash}TIM1_CH3N{slash}TIM3_CH4{slash}TIM8_CH3N{slash}OTG_HS_INTN{slash}ETH_MII_RXD3{slash}ADC12_IN9-Pad47)") (class "Default")
      (node (ref "U1") (pin "47") (pinfunction "PB1/TIM1_CH3N/TIM3_CH4/TIM8_CH3N/OTG_HS_INTN/ETH_MII_RXD3/ADC12_IN9_47") (pintype "passive"))
    )
    (net (code "208") (name "unconnected-(U1-PB11{slash}TIM2_CH4{slash}U3_RX{slash}I2C2_SDA{slash}HS_ULPI_D4{slash}ETH_MII_TX_EN{slash}ETH_RMII_TX_EN-Pad70)") (class "Default")
      (node (ref "U1") (pin "70") (pinfunction "PB11/TIM2_CH4/U3_RX/I2C2_SDA/HS_ULPI_D4/ETH_MII_TX_EN/ETH_RMII_TX_EN_70") (pintype "passive"))
    )
    (net (code "209") (name "unconnected-(U1-PC0{slash}OTG_HS_ULPI_STP{slash}ADC123_IN10-Pad26)") (class "Default")
      (node (ref "U1") (pin "26") (pinfunction "PC0/OTG_HS_ULPI_STP/ADC123_IN10_26") (pintype "passive"))
    )
    (net (code "210") (name "unconnected-(U1-PC13{slash}RTC_AF1-Pad7)") (class "Default")
      (node (ref "U1") (pin "7") (pinfunction "PC13/RTC_AF1_7") (pintype "passive"))
    )
    (net (code "211") (name "unconnected-(U1-PC14-OSC32_IN-Pad8)") (class "Default")
      (node (ref "U1") (pin "8") (pinfunction "PC14-OSC32_IN_8") (pintype "passive"))
    )
    (net (code "212") (name "unconnected-(U1-PC15-OSC32_OUT-Pad9)") (class "Default")
      (node (ref "U1") (pin "9") (pinfunction "PC15-OSC32_OUT_9") (pintype "passive"))
    )
    (net (code "213") (name "unconnected-(U1-PD7{slash}FSMC_NE1{slash}FSMC_NCE2{slash}U2_CK-Pad123)") (class "Default")
      (node (ref "U1") (pin "123") (pinfunction "PD7/FSMC_NE1/FSMC_NCE2/U2_CK_123") (pintype "passive"))
    )
    (net (code "214") (name "unconnected-(U1-PD10{slash}FSMC_D15{slash}U3_CK-Pad79)") (class "Default")
      (node (ref "U1") (pin "79") (pinfunction "PD10/FSMC_D15/U3_CK_79") (pintype "passive"))
    )
    (net (code "215") (name "unconnected-(U1-PD11{slash}FSMC_A16{slash}FSMC_CLE{slash}U3_CTS-Pad80)") (class "Default")
      (node (ref "U1") (pin "80") (pinfunction "PD11/FSMC_A16/FSMC_CLE/U3_CTS_80") (pintype "passive"))
    )
    (net (code "216") (name "unconnected-(U1-PE2{slash}TRACECLK{slash}FSMC_A23{slash}ETH_MII_TXD3-Pad1)") (class "Default")
      (node (ref "U1") (pin "1") (pinfunction "PE2/TRACECLK/FSMC_A23/ETH_MII_TXD3_1") (pintype "passive"))
    )
    (net (code "217") (name "unconnected-(U1-PE3{slash}TRACED0{slash}FSMC_A19-Pad2)") (class "Default")
      (node (ref "U1") (pin "2") (pinfunction "PE3/TRACED0/FSMC_A19_2") (pintype "passive"))
    )
    (net (code "218") (name "unconnected-(U1-PE12{slash}FSMC_D9{slash}TIM1_CH3N-Pad65)") (class "Default")
      (node (ref "U1") (pin "65") (pinfunction "PE12/FSMC_D9/TIM1_CH3N_65") (pintype "passive"))
    )
    (net (code "219") (name "unconnected-(U1-PF11{slash}DCMI_D12-Pad49)") (class "Default")
      (node (ref "U1") (pin "49") (pinfunction "PF11/DCMI_D12_49") (pintype "passive"))
    )
    (net (code "220") (name "unconnected-(U1-PG2{slash}FSMC_A12-Pad87)") (class "Default")
      (node (ref "U1") (pin "87") (pinfunction "PG2/FSMC_A12_87") (pintype "passive"))
    )
    (net (code "221") (name "unconnected-(U1-PG3{slash}FSMC_A13-Pad88)") (class "Default")
      (node (ref "U1") (pin "88") (pinfunction "PG3/FSMC_A13_88") (pintype "passive"))
    )
    (net (code "222") (name "unconnected-(U1-PG4{slash}FSMC_A14-Pad89)") (class "Default")
      (node (ref "U1") (pin "89") (pinfunction "PG4/FSMC_A14_89") (pintype "passive"))
    )
    (net (code "223") (name "unconnected-(U1-PG5{slash}FSMC_A15-Pad90)") (class "Default")
      (node (ref "U1") (pin "90") (pinfunction "PG5/FSMC_A15_90") (pintype "passive"))
    )
    (net (code "224") (name "unconnected-(U1-PG6{slash}FSMC_INT2-Pad91)") (class "Default")
      (node (ref "U1") (pin "91") (pinfunction "PG6/FSMC_INT2_91") (pintype "passive"))
    )
    (net (code "225") (name "unconnected-(U1-PG7{slash}FSMC_INT3{slash}U6_CK-Pad92)") (class "Default")
      (node (ref "U1") (pin "92") (pinfunction "PG7/FSMC_INT3/U6_CK_92") (pintype "passive"))
    )
    (net (code "226") (name "unconnected-(U1-PG8{slash}U6_RTS{slash}ETH_PPS_OUT-Pad93)") (class "Default")
      (node (ref "U1") (pin "93") (pinfunction "PG8/U6_RTS/ETH_PPS_OUT_93") (pintype "passive"))
    )
    (net (code "227") (name "unconnected-(U1-PG9{slash}FSMC_NE2{slash}FSMC_NCE3{slash}U6_RX-Pad124)") (class "Default")
      (node (ref "U1") (pin "124") (pinfunction "PG9/FSMC_NE2/FSMC_NCE3/U6_RX_124") (pintype "passive"))
    )
    (net (code "228") (name "unconnected-(U1-PG12{slash}FSMC_NE4{slash}U6_RTS-Pad127)") (class "Default")
      (node (ref "U1") (pin "127") (pinfunction "PG12/FSMC_NE4/U6_RTS_127") (pintype "passive"))
    )
    (net (code "229") (name "unconnected-(U2-Vref-Pad5)") (class "Default")
      (node (ref "U2") (pin "5") (pinfunction "Vref_5") (pintype "passive"))
    )
    (net (code "230") (name "unconnected-(U4-Vref-Pad5)") (class "Default")
      (node (ref "U4") (pin "5") (pinfunction "Vref_5") (pintype "passive"))
    )
    (net (code "231") (name "unconnected-(U6-NC-Pad5)") (class "Default")
      (node (ref "U6") (pin "5") (pinfunction "NC_5") (pintype "passive"))
    )
    (net (code "232") (name "unconnected-(U6-NC-Pad6)") (class "Default")
      (node (ref "U6") (pin "6") (pinfunction "NC_6") (pintype "passive"))
    )
    (net (code "233") (name "unconnected-(U6-NC-Pad19)") (class "Default")
      (node (ref "U6") (pin "19") (pinfunction "NC_19") (pintype "passive"))
    )
    (net (code "234") (name "unconnected-(U6-NC-Pad30)") (class "Default")
      (node (ref "U6") (pin "30") (pinfunction "NC_30") (pintype "passive"))
    )
    (net (code "235") (name "unconnected-(U6-NC-Pad31)") (class "Default")
      (node (ref "U6") (pin "31") (pinfunction "NC_31") (pintype "passive"))
    )
    (net (code "236") (name "unconnected-(U6-NC-Pad32)") (class "Default")
      (node (ref "U6") (pin "32") (pinfunction "NC_32") (pintype "passive"))
    )
    (net (code "237") (name "unconnected-(U6-NC-Pad33)") (class "Default")
      (node (ref "U6") (pin "33") (pinfunction "NC_33") (pintype "passive"))
    )
    (net (code "238") (name "unconnected-(U6-NC-Pad34)") (class "Default")
      (node (ref "U6") (pin "34") (pinfunction "NC_34") (pintype "passive"))
    )
    (net (code "239") (name "unconnected-(U6-NC-Pad35)") (class "Default")
      (node (ref "U6") (pin "35") (pinfunction "NC_35") (pintype "passive"))
    )
    (net (code "240") (name "unconnected-(U6-NC-Pad38)") (class "Default")
      (node (ref "U6") (pin "38") (pinfunction "NC_38") (pintype "passive"))
    )
    (net (code "241") (name "unconnected-(U6-NC-Pad58)") (class "Default")
      (node (ref "U6") (pin "58") (pinfunction "NC_58") (pintype "passive"))
    )
    (net (code "242") (name "unconnected-(U6-NC-Pad61)") (class "Default")
      (node (ref "U6") (pin "61") (pinfunction "NC_61") (pintype "passive"))
    )
    (net (code "243") (name "unconnected-(U6-NC-Pad63)") (class "Default")
      (node (ref "U6") (pin "63") (pinfunction "NC_63") (pintype "passive"))
    )
    (net (code "244") (name "unconnected-(U7-DIN2-Pad10)") (class "Default")
      (node (ref "U7") (pin "10") (pinfunction "DIN2_10") (pintype "passive"))
    )
    (net (code "245") (name "unconnected-(U7-DOUT2-Pad7)") (class "Default")
      (node (ref "U7") (pin "7") (pinfunction "DOUT2_7") (pintype "passive"))
    )
    (net (code "246") (name "unconnected-(U7-RIN2-Pad8)") (class "Default")
      (node (ref "U7") (pin "8") (pinfunction "RIN2_8") (pintype "passive"))
    )
    (net (code "247") (name "unconnected-(U7-ROUT2-Pad9)") (class "Default")
      (node (ref "U7") (pin "9") (pinfunction "ROUT2_9") (pintype "passive"))
    )
    (net (code "248") (name "unconnected-(U11B-V+-Pad4)") (class "Default")
      (node (ref "U11") (pin "4") (pinfunction "V+_4") (pintype "power_in"))
    )
    (net (code "249") (name "unconnected-(U11B-V--Pad11)") (class "Default")
      (node (ref "U11") (pin "11") (pinfunction "V-_11") (pintype "power_in"))
    )
    (net (code "250") (name "unconnected-(U11C-V+-Pad4)") (class "Default")
      (node (ref "U11") (pin "4") (pinfunction "V+_4") (pintype "power_in"))
    )
    (net (code "251") (name "unconnected-(U11C-V--Pad11)") (class "Default")
      (node (ref "U11") (pin "11") (pinfunction "V-_11") (pintype "power_in"))
    )
  )
)
